# Tractive_System_Board_Rev1.net
KiCad netlist of a schematic drawn in EAGLE
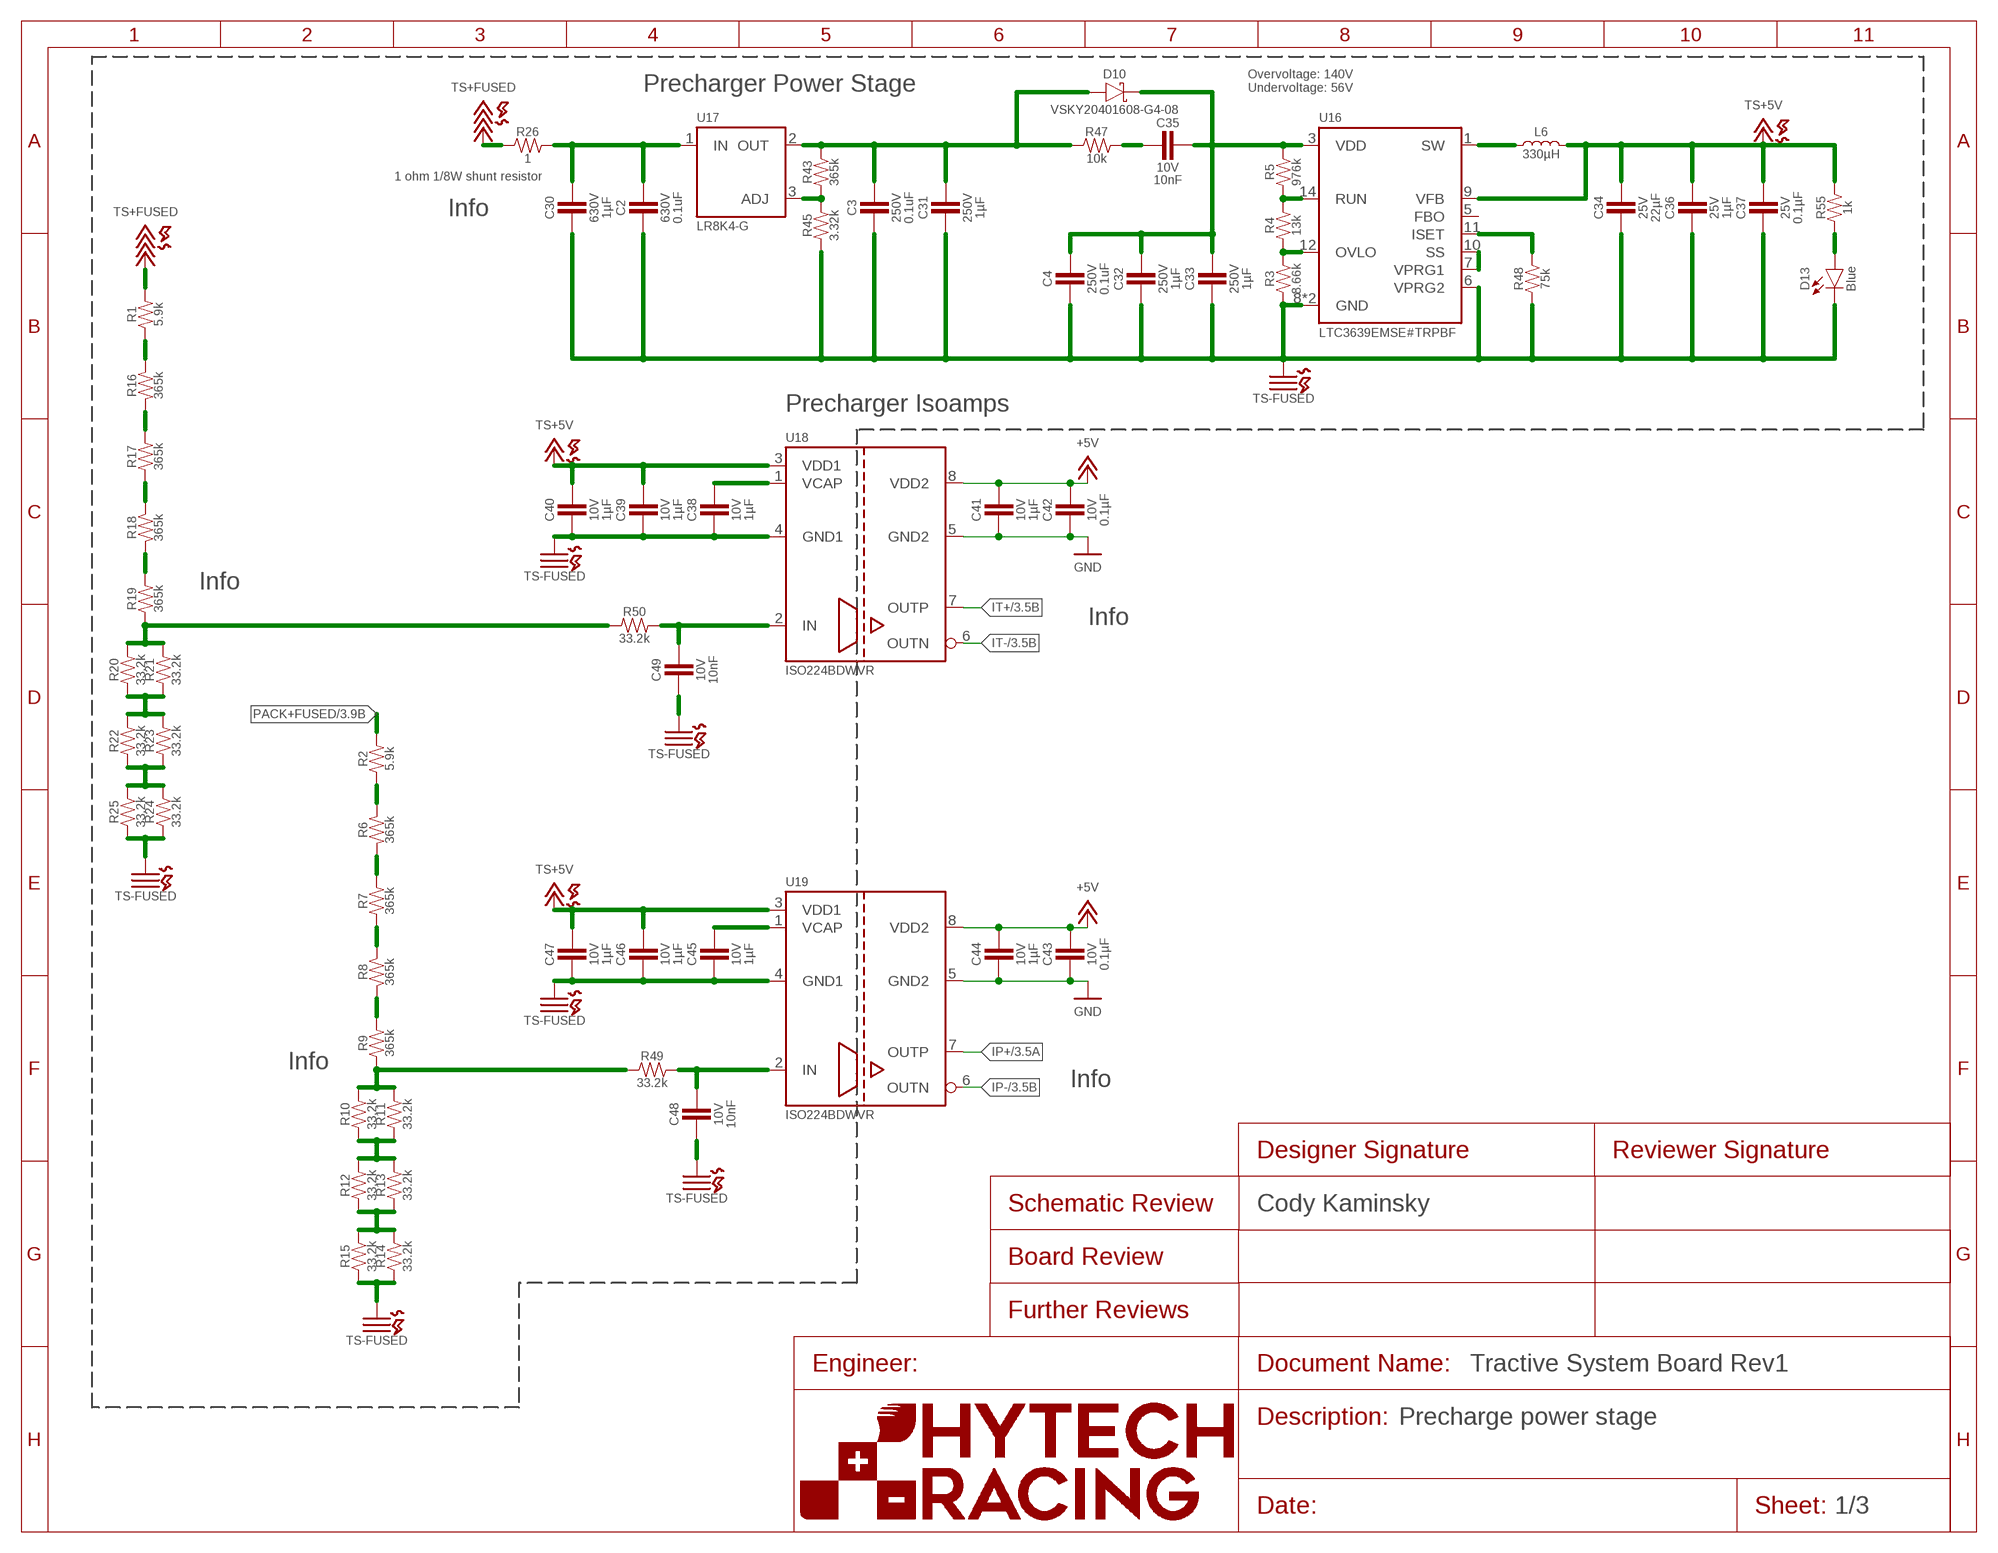
[diagram p0: schematic, sheet 1]
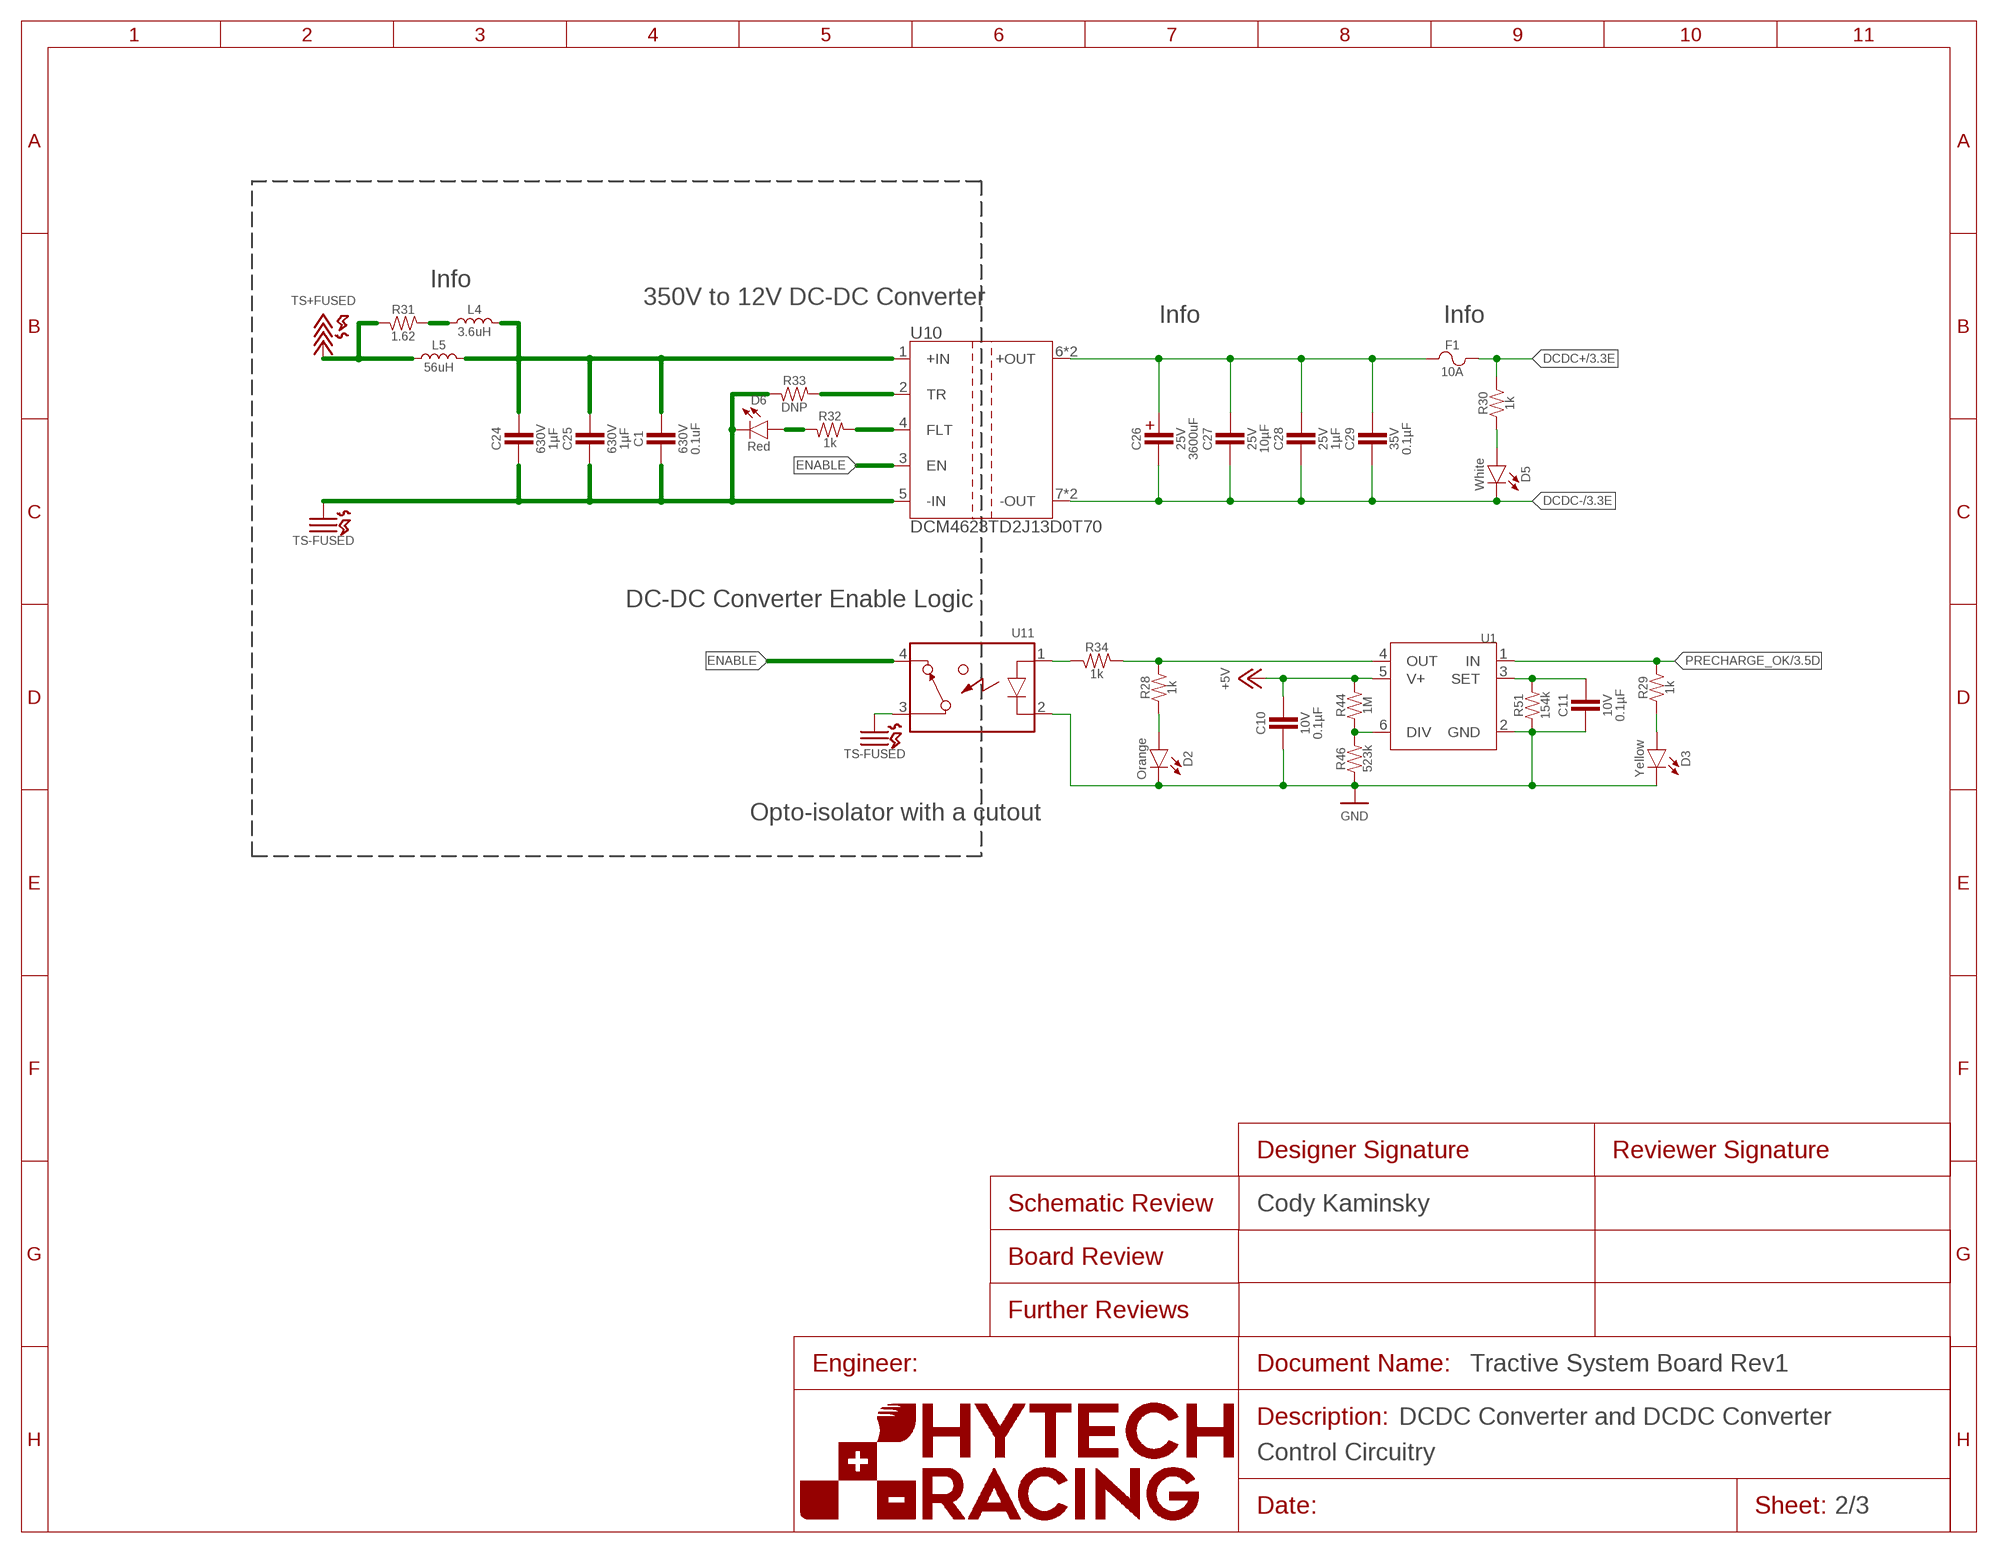
[diagram p1: schematic, sheet 2]
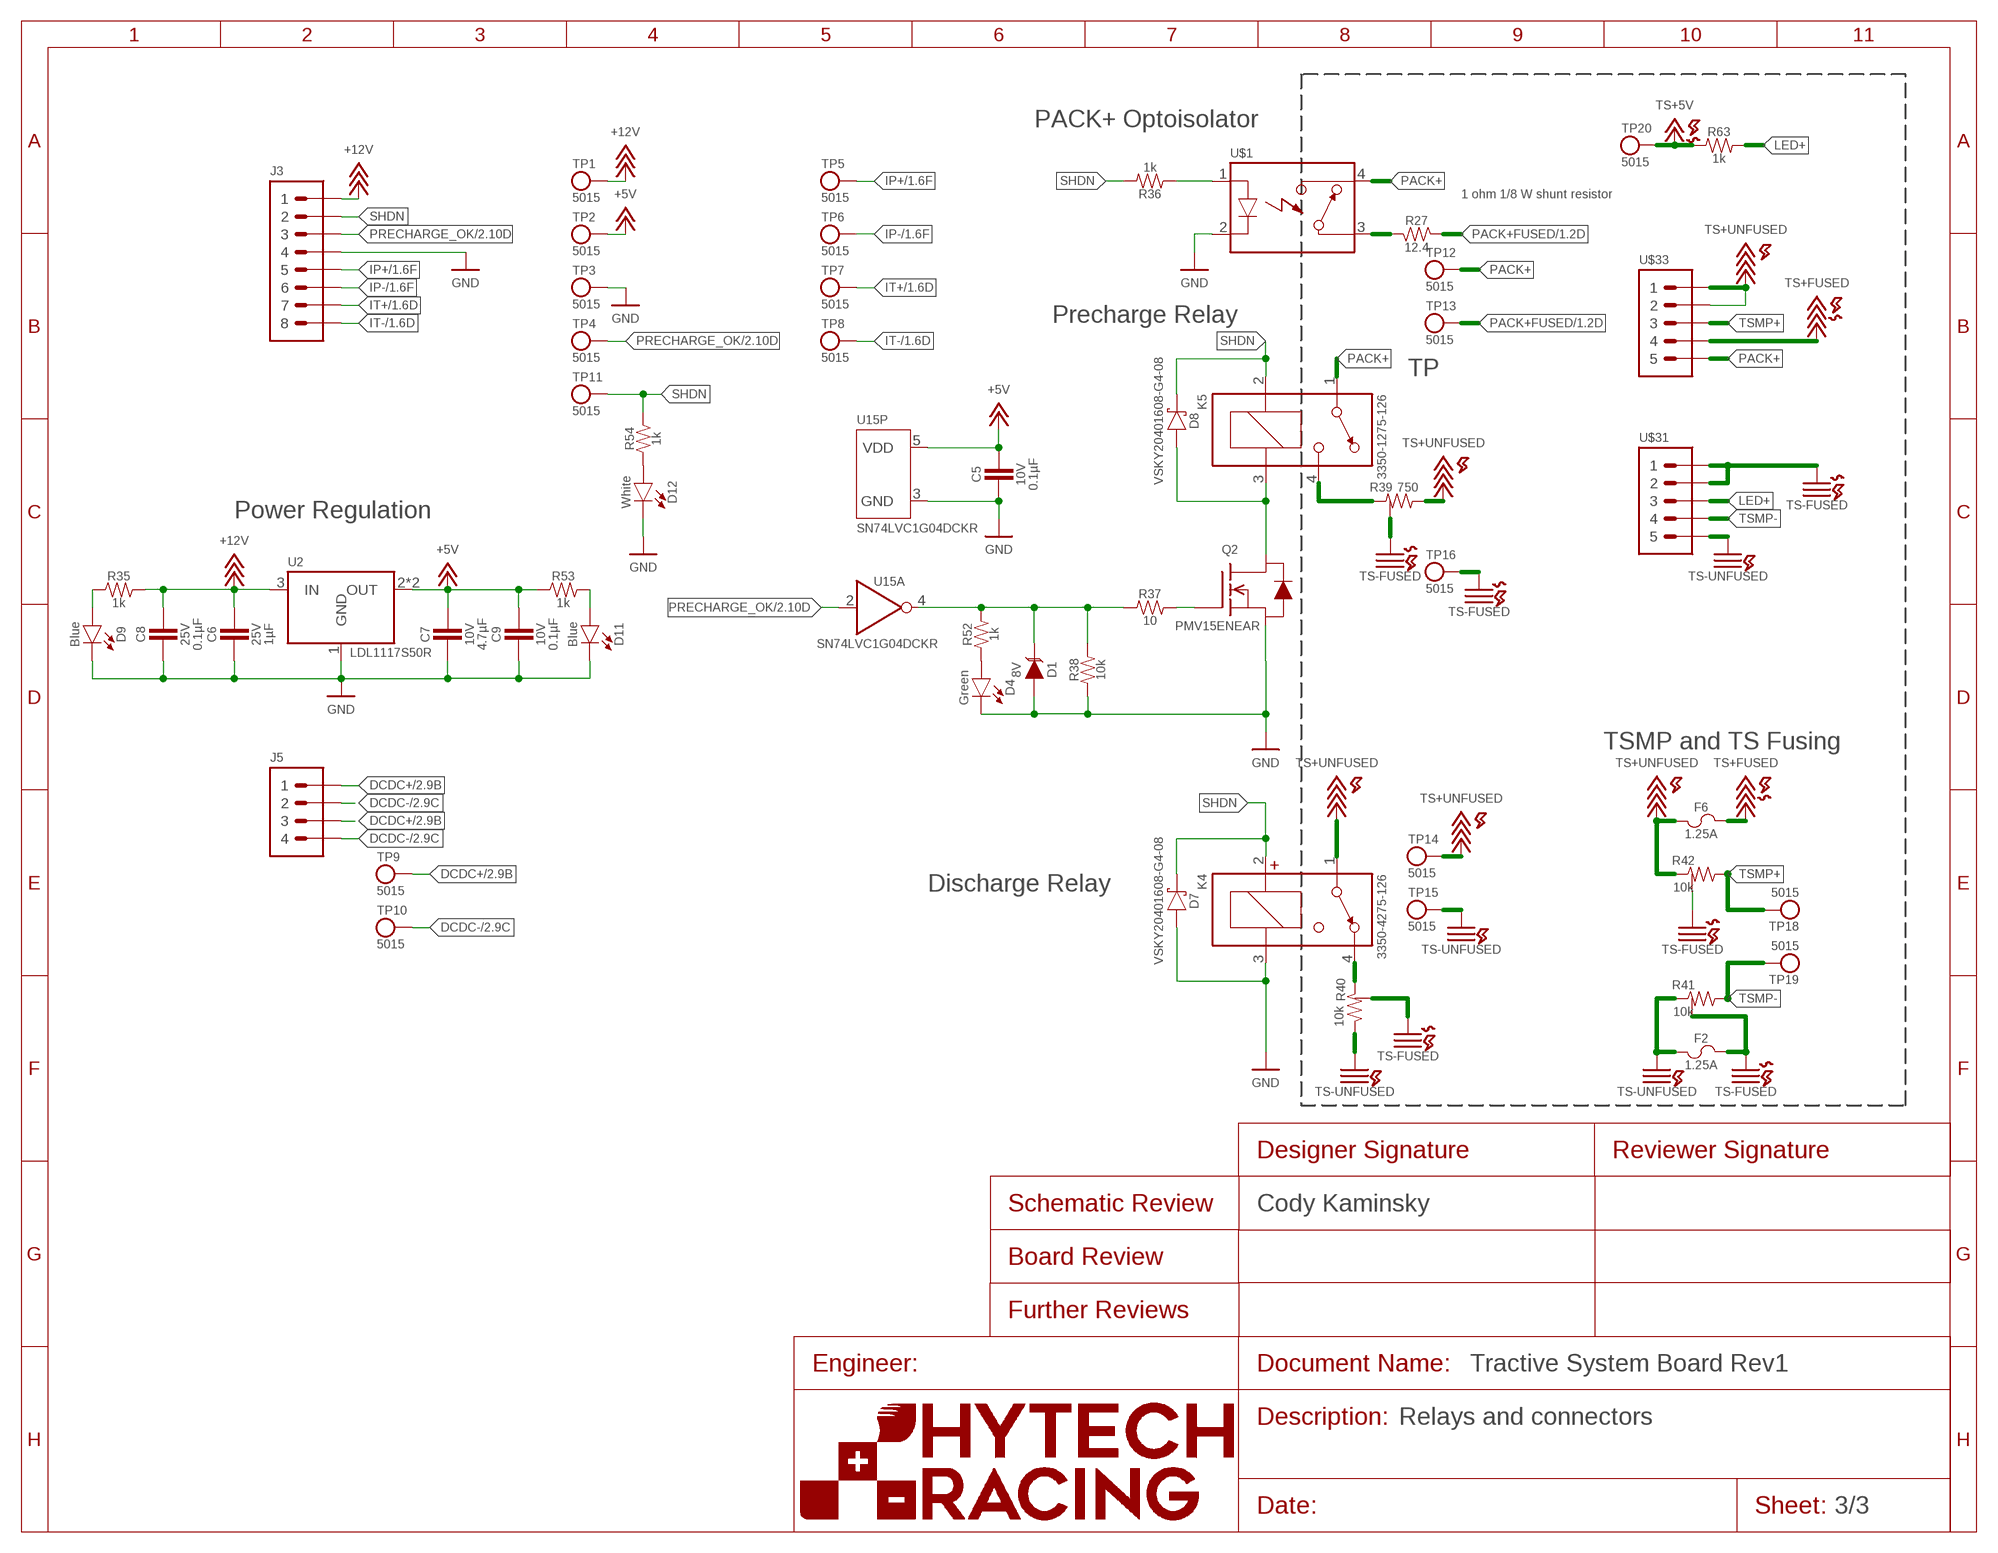
[diagram p2: schematic, sheet 3]

(export (version "E")
  (design (tool "Eeschema 10.0.6"))
  (components
    (comp (ref "C1")
      (value "CAPACITOR_2220_630V_0.1UF")
      (footprint "eagle-import:2220-CAP")
      (fields
        (field (name "CAPACITANCE") "0.1uF")
        (field (name "MANUFACTURER") "TDK Coporation")
        (field (name "MPN") "C5750CH2J104K280KC")
        (field (name "TOLERANCE") "10%")
        (field (name "VOLTAGE") "630V")
      )
      (libsource (lib "eagle-import") (part "CAPACITOR_?_2220630V_0.1UF"))
    )
    (comp (ref "C10")
      (value "CAPACITOR_0603_10V_0.1UF")
      (footprint "eagle-import:0603-CAP")
      (fields
        (field (name "CAPACITANCE") "0.1µF")
        (field (name "MANUFACTURER") "Vishay Vitramon")
        (field (name "MPN") "VJ0603Y104JXQPW1BC")
        (field (name "TOLERANCE") "5%")
        (field (name "VOLTAGE") "10V")
      )
      (libsource (lib "eagle-import") (part "CAPACITOR_?_060310V_0.1UF"))
    )
    (comp (ref "C11")
      (value "CAPACITOR_0603_10V_0.1UF")
      (footprint "eagle-import:0603-CAP")
      (fields
        (field (name "CAPACITANCE") "0.1µF")
        (field (name "MANUFACTURER") "Vishay Vitramon")
        (field (name "MPN") "VJ0603Y104JXQPW1BC")
        (field (name "TOLERANCE") "5%")
        (field (name "VOLTAGE") "10V")
      )
      (libsource (lib "eagle-import") (part "CAPACITOR_?_060310V_0.1UF"))
    )
    (comp (ref "C24")
      (value "CAPACITOR_2220_630V_1UF")
      (footprint "eagle-import:2220-CAP")
      (fields
        (field (name "CAPACITANCE") "1µF")
        (field (name "MANUFACTURER") "Knowles Syfer")
        (field (name "MPN") "2220Y6300105KXTWS2")
        (field (name "TOLERANCE") "10%")
        (field (name "VOLTAGE") "630V")
      )
      (libsource (lib "eagle-import") (part "CAPACITOR_?_2220630V_1UF"))
    )
    (comp (ref "C25")
      (value "CAPACITOR_2220_630V_1UF")
      (footprint "eagle-import:2220-CAP")
      (fields
        (field (name "CAPACITANCE") "1µF")
        (field (name "MANUFACTURER") "Knowles Syfer")
        (field (name "MPN") "2220Y6300105KXTWS2")
        (field (name "TOLERANCE") "10%")
        (field (name "VOLTAGE") "630V")
      )
      (libsource (lib "eagle-import") (part "CAPACITOR_?_2220630V_1UF"))
    )
    (comp (ref "C26")
      (value "CAPACITOR_POLAR__3600UF")
      (footprint "eagle-import:EKYC_MM")
      (fields
        (field (name "CAPACITANCE") "3600uF")
        (field (name "MANUFACTURER") "United Chemi-con")
        (field (name "MPN") "EKYC250ELL362ML20S")
        (field (name "VOLTAGE") "25V")
      )
      (libsource (lib "eagle-import") (part "CAPACITOR_POLAR_?_3600UF"))
    )
    (comp (ref "C27")
      (value "CAPACITOR_0603_25V_10UF")
      (footprint "eagle-import:0603-CAP")
      (fields
        (field (name "CAPACITANCE") "10µF")
        (field (name "MANUFACTURER") "Murata Electronics")
        (field (name "MPN") "GRM188R61E106MA73D")
        (field (name "TOLERANCE") "20%")
        (field (name "VOLTAGE") "25V")
      )
      (libsource (lib "eagle-import") (part "CAPACITOR_?_060325V_10UF"))
    )
    (comp (ref "C28")
      (value "CAPACITOR_0603_25V_1UF")
      (footprint "eagle-import:0603-CAP")
      (fields
        (field (name "CAPACITANCE") "1µF")
        (field (name "MANUFACTURER") "Samsung Electro-Mechanics")
        (field (name "MPN") "CL10B105KA8NNNC")
        (field (name "TOLERANCE") "10%")
        (field (name "VOLTAGE") "25V")
      )
      (libsource (lib "eagle-import") (part "CAPACITOR_?_060325V_1UF"))
    )
    (comp (ref "C29")
      (value "CAPACITOR_0603_35V_0.1UF")
      (footprint "eagle-import:0603-CAP")
      (fields
        (field (name "CAPACITANCE") "0.1µF")
        (field (name "MANUFACTURER") "Taiyo Yuden")
        (field (name "MPN") "GMK107B7104KAHT")
        (field (name "TOLERANCE") "10%")
        (field (name "VOLTAGE") "35V")
      )
      (libsource (lib "eagle-import") (part "CAPACITOR_?_060335V_0.1UF"))
    )
    (comp (ref "D2")
      (value "LED_0603_ORANGE")
      (footprint "eagle-import:0603-LED")
      (fields
        (field (name "COLOR") "Orange")
        (field (name "MANUFACTURER") "Kingbright")
        (field (name "MPN") "APT1608SECK")
      )
      (libsource (lib "eagle-import") (part "LED_?_0603ORANGE"))
    )
    (comp (ref "D3")
      (value "LED_0603_YELLOW")
      (footprint "eagle-import:0603-LED")
      (fields
        (field (name "COLOR") "Yellow")
        (field (name "MANUFACTURER") "Kingbright")
        (field (name "MPN") "APT1608SYCK/J3-PRV")
      )
      (libsource (lib "eagle-import") (part "LED_?_0603YELLOW"))
    )
    (comp (ref "D5")
      (value "LED_0603_WHITE")
      (footprint "eagle-import:0603-LED")
      (fields
        (field (name "COLOR") "White")
        (field (name "MANUFACTURER") "Bivar Inc.")
        (field (name "MPN") "SM0603UWC")
      )
      (libsource (lib "eagle-import") (part "LED_?_0603WHITE"))
    )
    (comp (ref "D6")
      (value "LED_0603_RED")
      (footprint "eagle-import:0603-LED")
      (fields
        (field (name "COLOR") "Red")
        (field (name "MANUFACTURER") "Kingbright")
        (field (name "MPN") "APT1608SECK/J3-PRV")
      )
      (libsource (lib "eagle-import") (part "LED_?_0603RED"))
    )
    (comp (ref "F1")
      (value "FUSE_MB_10")
      (footprint "eagle-import:MINI-BLADE_FUSE_HOLDER")
      (fields
        (field (name "CURRENT") "10A")
        (field (name "MANUFACTURER") "Littelfuse Inc.")
        (field (name "MPN") "0297010.WXNV")
        (field (name "VOLTAGE") "32V")
      )
      (libsource (lib "eagle-import") (part "FUSE_?_MB10"))
    )
    (comp (ref "L4")
      (value "INDUCTOR_PA4334_3.6UH")
      (footprint "eagle-import:PA4334")
      (fields
        (field (name "INDUCTANCE") "3.6uH")
        (field (name "MANUFACTURER") "Pulse Electonics Company")
        (field (name "MPN") "PA4334.362NLT")
        (field (name "TOLERANCE") "20%")
      )
      (libsource (lib "eagle-import") (part "INDUCTOR_?_PA43343.6UH"))
    )
    (comp (ref "L5")
      (value "INDUCTOR_WELMHI_56UH")
      (footprint "eagle-import:WE-LMHI")
      (fields
        (field (name "INDUCTANCE") "56uH")
        (field (name "MANUFACTURER") "Wurth Elektronik")
        (field (name "MPN") "74437349560")
        (field (name "TOLERANCE") "20%")
      )
      (libsource (lib "eagle-import") (part "INDUCTOR_?_WELMHI56UH"))
    )
    (comp (ref "R28")
      (value "RESISTOR_0603_1K")
      (footprint "eagle-import:0603-RES")
      (fields
        (field (name "MANUFACTURER") "Yageo")
        (field (name "MPN") "RC0603FR-071KL")
        (field (name "POWER") "0.1W")
        (field (name "RESISTANCE") "1k")
      )
      (libsource (lib "eagle-import") (part "RESISTOR_?_06031K"))
    )
    (comp (ref "R29")
      (value "RESISTOR_0603_1K")
      (footprint "eagle-import:0603-RES")
      (fields
        (field (name "MANUFACTURER") "Yageo")
        (field (name "MPN") "RC0603FR-071KL")
        (field (name "POWER") "0.1W")
        (field (name "RESISTANCE") "1k")
      )
      (libsource (lib "eagle-import") (part "RESISTOR_?_06031K"))
    )
    (comp (ref "R30")
      (value "RESISTOR_0603_1K")
      (footprint "eagle-import:0603-RES")
      (fields
        (field (name "MANUFACTURER") "Yageo")
        (field (name "MPN") "RC0603FR-071KL")
        (field (name "POWER") "0.1W")
        (field (name "RESISTANCE") "1k")
      )
      (libsource (lib "eagle-import") (part "RESISTOR_?_06031K"))
    )
    (comp (ref "R31")
      (value "RESISTOR_0603_1.62")
      (footprint "eagle-import:0603-RES")
      (fields
        (field (name "MANUFACTURER") "TE Conductivity Passive Product")
        (field (name "MPN") "CPF0603B1R62E1")
        (field (name "POWER") "0.1W")
        (field (name "RESISTANCE") "1.62")
      )
      (libsource (lib "eagle-import") (part "RESISTOR_?_06031.62"))
    )
    (comp (ref "R32")
      (value "RESISTOR_0603_1K")
      (footprint "eagle-import:0603-RES")
      (fields
        (field (name "MANUFACTURER") "Yageo")
        (field (name "MPN") "RC0603FR-071KL")
        (field (name "POWER") "0.1W")
        (field (name "RESISTANCE") "1k")
      )
      (libsource (lib "eagle-import") (part "RESISTOR_?_06031K"))
    )
    (comp (ref "R33")
      (value "RESISTOR_0603_DNP")
      (footprint "eagle-import:0603-RES")
      (fields (field (name "RESISTANCE") "DNP"))
      (libsource (lib "eagle-import") (part "RESISTOR_?_0603DNP"))
    )
    (comp (ref "R34")
      (value "RESISTOR_0603_1K")
      (footprint "eagle-import:0603-RES")
      (fields
        (field (name "MANUFACTURER") "Yageo")
        (field (name "MPN") "RC0603FR-071KL")
        (field (name "POWER") "0.1W")
        (field (name "RESISTANCE") "1k")
      )
      (libsource (lib "eagle-import") (part "RESISTOR_?_06031K"))
    )
    (comp (ref "R44")
      (value "RESISTOR_0805_1M")
      (footprint "eagle-import:0805-RES")
      (fields
        (field (name "MANUFACTURER") "Panasonic Electronic Components")
        (field (name "MPN") "ERJ-PB6B1004V")
        (field (name "POWER") "0.25W")
        (field (name "RESISTANCE") "1M")
      )
      (libsource (lib "eagle-import") (part "RESISTOR_?_08051M"))
    )
    (comp (ref "R46")
      (value "RESISTOR_0805_523K")
      (footprint "eagle-import:0805-RES")
      (fields
        (field (name "MANUFACTURER") "Panasonic Electronic Components")
        (field (name "MPN") "ERJ-PB6B5233V")
        (field (name "POWER") "0.25W")
        (field (name "RESISTANCE") "523k")
      )
      (libsource (lib "eagle-import") (part "RESISTOR_?_0805523K"))
    )
    (comp (ref "R51")
      (value "RESISTOR_0603_154K")
      (footprint "eagle-import:0603-RES")
      (fields
        (field (name "MANUFACTURER") "Panasonic Electronic Components")
        (field (name "MPN") "ERA-3AEB1543V")
        (field (name "POWER") "0.1W")
        (field (name "RESISTANCE") "154k")
      )
      (libsource (lib "eagle-import") (part "RESISTOR_?_0603154K"))
    )
    (comp (ref "U1")
      (value "LTC6994_1")
      (footprint "eagle-import:SOT-23-6")
      (fields (field (name "MANUFACTURER") "Analog Electronics") (field (name "MPN") "LTC6994CS6-1#TRMPBF"))
      (libsource (lib "eagle-import") (part "LTC6994_1"))
    )
    (comp (ref "U10")
      (value "DCM4623TD2J13D0T70")
      (footprint "eagle-import:DCM4623")
      (fields (field (name "MANUFACTURER") "Vicor"))
      (libsource (lib "eagle-import") (part "DCM4623TD2J13D0T70"))
    )
    (comp (ref "U11")
      (value "RELAY_SOLIDSTATE_NC_AG")
      (footprint "eagle-import:DIP-4_AIRGAP")
      (fields (field (name "MPN") "AQY414EHA") (field (name "MANUFACTURER") "Panasonic Industrial Devices"))
      (libsource (lib "eagle-import") (part "RELAY_SOLIDSTATE_NC_?AG"))
    )
    (comp (ref "C2")
      (value "CAPACITOR_2220_630V_0.1UF")
      (footprint "eagle-import:2220-CAP")
      (fields
        (field (name "CAPACITANCE") "0.1uF")
        (field (name "MANUFACTURER") "TDK Coporation")
        (field (name "MPN") "C5750CH2J104K280KC")
        (field (name "TOLERANCE") "10%")
        (field (name "VOLTAGE") "630V")
      )
      (libsource (lib "eagle-import") (part "CAPACITOR_?_2220630V_0.1UF"))
    )
    (comp (ref "C3")
      (value "CAPACITOR_1206_250V_0.1UF")
      (footprint "eagle-import:1206-CAP")
      (fields
        (field (name "CAPACITANCE") "0.1uF")
        (field (name "MANUFACTURER") "TDK Corporation")
        (field (name "MPN") "C3216X7R2E104K160AM")
        (field (name "TOLERANCE") "10%")
        (field (name "VOLTAGE") "250V")
      )
      (libsource (lib "eagle-import") (part "CAPACITOR_?_1206250V_0.1UF"))
    )
    (comp (ref "C4")
      (value "CAPACITOR_1206_250V_0.1UF")
      (footprint "eagle-import:1206-CAP")
      (fields
        (field (name "CAPACITANCE") "0.1uF")
        (field (name "MANUFACTURER") "TDK Corporation")
        (field (name "MPN") "C3216X7R2E104K160AM")
        (field (name "TOLERANCE") "10%")
        (field (name "VOLTAGE") "250V")
      )
      (libsource (lib "eagle-import") (part "CAPACITOR_?_1206250V_0.1UF"))
    )
    (comp (ref "C30")
      (value "CAPACITOR_2220_630V_1UF")
      (footprint "eagle-import:2220-CAP")
      (fields
        (field (name "CAPACITANCE") "1µF")
        (field (name "MANUFACTURER") "Knowles Syfer")
        (field (name "MPN") "2220Y6300105KXTWS2")
        (field (name "TOLERANCE") "10%")
        (field (name "VOLTAGE") "630V")
      )
      (libsource (lib "eagle-import") (part "CAPACITOR_?_2220630V_1UF"))
    )
    (comp (ref "C31")
      (value "CAPACITOR_2220_250V_1UF")
      (footprint "eagle-import:2220-CAP")
      (fields
        (field (name "CAPACITANCE") "1µF")
        (field (name "MANUFACTURER") "TDK Corporation")
        (field (name "MPN") "C5750X7R2E105K230KA")
        (field (name "TOLERANCE") "10%")
        (field (name "VOLTAGE") "250V")
      )
      (libsource (lib "eagle-import") (part "CAPACITOR_?_2220250V_1UF"))
    )
    (comp (ref "C32")
      (value "CAPACITOR_2220_250V_1UF")
      (footprint "eagle-import:2220-CAP")
      (fields
        (field (name "CAPACITANCE") "1µF")
        (field (name "MANUFACTURER") "TDK Corporation")
        (field (name "MPN") "C5750X7R2E105K230KA")
        (field (name "TOLERANCE") "10%")
        (field (name "VOLTAGE") "250V")
      )
      (libsource (lib "eagle-import") (part "CAPACITOR_?_2220250V_1UF"))
    )
    (comp (ref "C33")
      (value "CAPACITOR_2220_250V_1UF")
      (footprint "eagle-import:2220-CAP")
      (fields
        (field (name "CAPACITANCE") "1µF")
        (field (name "MANUFACTURER") "TDK Corporation")
        (field (name "MPN") "C5750X7R2E105K230KA")
        (field (name "TOLERANCE") "10%")
        (field (name "VOLTAGE") "250V")
      )
      (libsource (lib "eagle-import") (part "CAPACITOR_?_2220250V_1UF"))
    )
    (comp (ref "C34")
      (value "CAPACITOR_0805_25V_22UF")
      (footprint "eagle-import:0805-CAP")
      (fields
        (field (name "CAPACITANCE") "22µF")
        (field (name "MANUFACTURER") "Yageo")
        (field (name "MPN") "CC0805MKX5R8BB226")
        (field (name "TOLERANCE") "20%")
        (field (name "VOLTAGE") "25V")
      )
      (libsource (lib "eagle-import") (part "CAPACITOR_?_080525V_22UF"))
    )
    (comp (ref "C35")
      (value "CAPACITOR_0603_10V_10NF")
      (footprint "eagle-import:0603-CAP")
      (fields
        (field (name "CAPACITANCE") "10nF")
        (field (name "MANUFACTURER") "Yageo")
        (field (name "MPN") "CC0603KRX7R6BB103")
        (field (name "TOLERANCE") "10%")
        (field (name "VOLTAGE") "10V")
      )
      (libsource (lib "eagle-import") (part "CAPACITOR_?_060310V_10NF"))
    )
    (comp (ref "C36")
      (value "CAPACITOR_0603_25V_1UF")
      (footprint "eagle-import:0603-CAP")
      (fields
        (field (name "CAPACITANCE") "1µF")
        (field (name "MANUFACTURER") "Samsung Electro-Mechanics")
        (field (name "MPN") "CL10B105KA8NNNC")
        (field (name "TOLERANCE") "10%")
        (field (name "VOLTAGE") "25V")
      )
      (libsource (lib "eagle-import") (part "CAPACITOR_?_060325V_1UF"))
    )
    (comp (ref "C37")
      (value "CAPACITOR_0603_25V_0.1UF")
      (footprint "eagle-import:0603-CAP")
      (fields
        (field (name "CAPACITANCE") "0.1µF")
        (field (name "MANUFACTURER") "Samsung Electro-Mechanics")
        (field (name "MPN") "CL10B104KA8NNNC")
        (field (name "TOLERANCE") "10%")
        (field (name "VOLTAGE") "25V")
      )
      (libsource (lib "eagle-import") (part "CAPACITOR_?_060325V_0.1UF"))
    )
    (comp (ref "C38")
      (value "CAPACITOR_0603_10V_1UF")
      (footprint "eagle-import:0603-CAP")
      (fields
        (field (name "CAPACITANCE") "1µF")
        (field (name "MANUFACTURER") "Yageo")
        (field (name "MPN") "CC0603KRX7R6BB105")
        (field (name "TOLERANCE") "10%")
        (field (name "VOLTAGE") "10V")
      )
      (libsource (lib "eagle-import") (part "CAPACITOR_?_060310V_1UF"))
    )
    (comp (ref "C39")
      (value "CAPACITOR_0603_10V_1UF")
      (footprint "eagle-import:0603-CAP")
      (fields
        (field (name "CAPACITANCE") "1µF")
        (field (name "MANUFACTURER") "Yageo")
        (field (name "MPN") "CC0603KRX7R6BB105")
        (field (name "TOLERANCE") "10%")
        (field (name "VOLTAGE") "10V")
      )
      (libsource (lib "eagle-import") (part "CAPACITOR_?_060310V_1UF"))
    )
    (comp (ref "C40")
      (value "CAPACITOR_0603_10V_1UF")
      (footprint "eagle-import:0603-CAP")
      (fields
        (field (name "CAPACITANCE") "1µF")
        (field (name "MANUFACTURER") "Yageo")
        (field (name "MPN") "CC0603KRX7R6BB105")
        (field (name "TOLERANCE") "10%")
        (field (name "VOLTAGE") "10V")
      )
      (libsource (lib "eagle-import") (part "CAPACITOR_?_060310V_1UF"))
    )
    (comp (ref "C41")
      (value "CAPACITOR_0603_10V_1UF")
      (footprint "eagle-import:0603-CAP")
      (fields
        (field (name "CAPACITANCE") "1µF")
        (field (name "MANUFACTURER") "Yageo")
        (field (name "MPN") "CC0603KRX7R6BB105")
        (field (name "TOLERANCE") "10%")
        (field (name "VOLTAGE") "10V")
      )
      (libsource (lib "eagle-import") (part "CAPACITOR_?_060310V_1UF"))
    )
    (comp (ref "C42")
      (value "CAPACITOR_0603_10V_0.1UF")
      (footprint "eagle-import:0603-CAP")
      (fields
        (field (name "CAPACITANCE") "0.1µF")
        (field (name "MANUFACTURER") "Vishay Vitramon")
        (field (name "MPN") "VJ0603Y104JXQPW1BC")
        (field (name "TOLERANCE") "5%")
        (field (name "VOLTAGE") "10V")
      )
      (libsource (lib "eagle-import") (part "CAPACITOR_?_060310V_0.1UF"))
    )
    (comp (ref "C43")
      (value "CAPACITOR_0603_10V_0.1UF")
      (footprint "eagle-import:0603-CAP")
      (fields
        (field (name "CAPACITANCE") "0.1µF")
        (field (name "MANUFACTURER") "Vishay Vitramon")
        (field (name "MPN") "VJ0603Y104JXQPW1BC")
        (field (name "TOLERANCE") "5%")
        (field (name "VOLTAGE") "10V")
      )
      (libsource (lib "eagle-import") (part "CAPACITOR_?_060310V_0.1UF"))
    )
    (comp (ref "C44")
      (value "CAPACITOR_0603_10V_1UF")
      (footprint "eagle-import:0603-CAP")
      (fields
        (field (name "CAPACITANCE") "1µF")
        (field (name "MANUFACTURER") "Yageo")
        (field (name "MPN") "CC0603KRX7R6BB105")
        (field (name "TOLERANCE") "10%")
        (field (name "VOLTAGE") "10V")
      )
      (libsource (lib "eagle-import") (part "CAPACITOR_?_060310V_1UF"))
    )
    (comp (ref "C45")
      (value "CAPACITOR_0603_10V_1UF")
      (footprint "eagle-import:0603-CAP")
      (fields
        (field (name "CAPACITANCE") "1µF")
        (field (name "MANUFACTURER") "Yageo")
        (field (name "MPN") "CC0603KRX7R6BB105")
        (field (name "TOLERANCE") "10%")
        (field (name "VOLTAGE") "10V")
      )
      (libsource (lib "eagle-import") (part "CAPACITOR_?_060310V_1UF"))
    )
    (comp (ref "C46")
      (value "CAPACITOR_0603_10V_1UF")
      (footprint "eagle-import:0603-CAP")
      (fields
        (field (name "CAPACITANCE") "1µF")
        (field (name "MANUFACTURER") "Yageo")
        (field (name "MPN") "CC0603KRX7R6BB105")
        (field (name "TOLERANCE") "10%")
        (field (name "VOLTAGE") "10V")
      )
      (libsource (lib "eagle-import") (part "CAPACITOR_?_060310V_1UF"))
    )
    (comp (ref "C47")
      (value "CAPACITOR_0603_10V_1UF")
      (footprint "eagle-import:0603-CAP")
      (fields
        (field (name "CAPACITANCE") "1µF")
        (field (name "MANUFACTURER") "Yageo")
        (field (name "MPN") "CC0603KRX7R6BB105")
        (field (name "TOLERANCE") "10%")
        (field (name "VOLTAGE") "10V")
      )
      (libsource (lib "eagle-import") (part "CAPACITOR_?_060310V_1UF"))
    )
    (comp (ref "C48")
      (value "CAPACITOR_0603_10V_10NF")
      (footprint "eagle-import:0603-CAP")
      (fields
        (field (name "CAPACITANCE") "10nF")
        (field (name "MANUFACTURER") "Yageo")
        (field (name "MPN") "CC0603KRX7R6BB103")
        (field (name "TOLERANCE") "10%")
        (field (name "VOLTAGE") "10V")
      )
      (libsource (lib "eagle-import") (part "CAPACITOR_?_060310V_10NF"))
    )
    (comp (ref "C49")
      (value "CAPACITOR_0603_10V_10NF")
      (footprint "eagle-import:0603-CAP")
      (fields
        (field (name "CAPACITANCE") "10nF")
        (field (name "MANUFACTURER") "Yageo")
        (field (name "MPN") "CC0603KRX7R6BB103")
        (field (name "TOLERANCE") "10%")
        (field (name "VOLTAGE") "10V")
      )
      (libsource (lib "eagle-import") (part "CAPACITOR_?_060310V_10NF"))
    )
    (comp (ref "D10")
      (value "SCHOTTKY")
      (footprint "eagle-import:CLP1608-2L")
      (fields
        (field (name "MPN") "VSKY20401608-G4-08")
        (field (name "MANUFACTURER") "Vishay General Semiconductor - Diodes Division")
      )
      (libsource (lib "eagle-import") (part "SCHOTTKY"))
    )
    (comp (ref "D13")
      (value "LED_0603_BLUE")
      (footprint "eagle-import:0603-LED")
      (fields
        (field (name "COLOR") "Blue")
        (field (name "MANUFACTURER") "Kingbright")
        (field (name "MPN") "APT1608VBC/D")
      )
      (libsource (lib "eagle-import") (part "LED_?_0603BLUE"))
    )
    (comp (ref "L6")
      (value "INDUCTOR_SRU1048_330UH")
      (footprint "eagle-import:SRU1048")
      (fields
        (field (name "INDUCTANCE") "330µH")
        (field (name "MANUFACTURER") "Bourns Inc.")
        (field (name "MPN") "SRU1048-331Y")
        (field (name "TOLERANCE") "30%")
      )
      (libsource (lib "eagle-import") (part "INDUCTOR_?_SRU1048330UH"))
    )
    (comp (ref "R1")
      (value "RESISTOR_0603_5.9K")
      (footprint "eagle-import:0603-RES")
      (fields
        (field (name "MANUFACTURER") "Panasonic Electronic Components")
        (field (name "MPN") "ERA-3AEB5901V")
        (field (name "POWER") "0.1W")
        (field (name "RESISTANCE") "5.9k")
      )
      (libsource (lib "eagle-import") (part "RESISTOR_?_06035.9K"))
    )
    (comp (ref "R2")
      (value "RESISTOR_0603_5.9K")
      (footprint "eagle-import:0603-RES")
      (fields
        (field (name "MANUFACTURER") "Panasonic Electronic Components")
        (field (name "MPN") "ERA-3AEB5901V")
        (field (name "POWER") "0.1W")
        (field (name "RESISTANCE") "5.9k")
      )
      (libsource (lib "eagle-import") (part "RESISTOR_?_06035.9K"))
    )
    (comp (ref "R3")
      (value "RESISTOR_0603_8.66K")
      (footprint "eagle-import:0603-RES")
      (fields
        (field (name "MANUFACTURER") "Yageo")
        (field (name "MPN") "RT0603BRD078K66L")
        (field (name "POWER") "0.1W")
        (field (name "RESISTANCE") "8.66k")
      )
      (libsource (lib "eagle-import") (part "RESISTOR_?_06038.66K"))
    )
    (comp (ref "R4")
      (value "RESISTOR_0603_13K")
      (footprint "eagle-import:0603-RES")
      (fields
        (field (name "MANUFACTURER") "Panasonic Electronic Components")
        (field (name "MPN") " ERJ-PB3B1302V")
        (field (name "POWER") "0.1W")
        (field (name "RESISTANCE") "13k")
      )
      (libsource (lib "eagle-import") (part "RESISTOR_?_060313K"))
    )
    (comp (ref "R5")
      (value "RESISTOR_0805_976K")
      (footprint "eagle-import:0805-RES")
      (fields
        (field (name "MANUFACTURER") "Panasonic Electronic Components")
        (field (name "MPN") "  ERJ-PB6B9763V")
        (field (name "POWER") "0.25W")
        (field (name "RESISTANCE") "976k")
      )
      (libsource (lib "eagle-import") (part "RESISTOR_?_0805976K"))
    )
    (comp (ref "R6")
      (value "RESISTOR_0805_365K")
      (footprint "eagle-import:0805-RES")
      (fields
        (field (name "MANUFACTURER") "Panasonic Electronic Components")
        (field (name "MPN") "ERJ-PB6B3653V")
        (field (name "POWER") "0.25W")
        (field (name "RESISTANCE") "365k")
      )
      (libsource (lib "eagle-import") (part "RESISTOR_?_0805365K"))
    )
    (comp (ref "R7")
      (value "RESISTOR_0805_365K")
      (footprint "eagle-import:0805-RES")
      (fields
        (field (name "MANUFACTURER") "Panasonic Electronic Components")
        (field (name "MPN") "ERJ-PB6B3653V")
        (field (name "POWER") "0.25W")
        (field (name "RESISTANCE") "365k")
      )
      (libsource (lib "eagle-import") (part "RESISTOR_?_0805365K"))
    )
    (comp (ref "R8")
      (value "RESISTOR_0805_365K")
      (footprint "eagle-import:0805-RES")
      (fields
        (field (name "MANUFACTURER") "Panasonic Electronic Components")
        (field (name "MPN") "ERJ-PB6B3653V")
        (field (name "POWER") "0.25W")
        (field (name "RESISTANCE") "365k")
      )
      (libsource (lib "eagle-import") (part "RESISTOR_?_0805365K"))
    )
    (comp (ref "R9")
      (value "RESISTOR_0805_365K")
      (footprint "eagle-import:0805-RES")
      (fields
        (field (name "MANUFACTURER") "Panasonic Electronic Components")
        (field (name "MPN") "ERJ-PB6B3653V")
        (field (name "POWER") "0.25W")
        (field (name "RESISTANCE") "365k")
      )
      (libsource (lib "eagle-import") (part "RESISTOR_?_0805365K"))
    )
    (comp (ref "R10")
      (value "RESISTOR_0603_33.2K")
      (footprint "eagle-import:0603-RES")
      (fields
        (field (name "MANUFACTURER") "Panasonic Electronic Components")
        (field (name "MPN") "ERJ-PB3B3322V")
        (field (name "POWER") "0.1W")
        (field (name "RESISTANCE") "33.2k")
      )
      (libsource (lib "eagle-import") (part "RESISTOR_?_060333.2K"))
    )
    (comp (ref "R11")
      (value "RESISTOR_0603_33.2K")
      (footprint "eagle-import:0603-RES")
      (fields
        (field (name "MANUFACTURER") "Panasonic Electronic Components")
        (field (name "MPN") "ERJ-PB3B3322V")
        (field (name "POWER") "0.1W")
        (field (name "RESISTANCE") "33.2k")
      )
      (libsource (lib "eagle-import") (part "RESISTOR_?_060333.2K"))
    )
    (comp (ref "R12")
      (value "RESISTOR_0603_33.2K")
      (footprint "eagle-import:0603-RES")
      (fields
        (field (name "MANUFACTURER") "Panasonic Electronic Components")
        (field (name "MPN") "ERJ-PB3B3322V")
        (field (name "POWER") "0.1W")
        (field (name "RESISTANCE") "33.2k")
      )
      (libsource (lib "eagle-import") (part "RESISTOR_?_060333.2K"))
    )
    (comp (ref "R13")
      (value "RESISTOR_0603_33.2K")
      (footprint "eagle-import:0603-RES")
      (fields
        (field (name "MANUFACTURER") "Panasonic Electronic Components")
        (field (name "MPN") "ERJ-PB3B3322V")
        (field (name "POWER") "0.1W")
        (field (name "RESISTANCE") "33.2k")
      )
      (libsource (lib "eagle-import") (part "RESISTOR_?_060333.2K"))
    )
    (comp (ref "R14")
      (value "RESISTOR_0603_33.2K")
      (footprint "eagle-import:0603-RES")
      (fields
        (field (name "MANUFACTURER") "Panasonic Electronic Components")
        (field (name "MPN") "ERJ-PB3B3322V")
        (field (name "POWER") "0.1W")
        (field (name "RESISTANCE") "33.2k")
      )
      (libsource (lib "eagle-import") (part "RESISTOR_?_060333.2K"))
    )
    (comp (ref "R15")
      (value "RESISTOR_0603_33.2K")
      (footprint "eagle-import:0603-RES")
      (fields
        (field (name "MANUFACTURER") "Panasonic Electronic Components")
        (field (name "MPN") "ERJ-PB3B3322V")
        (field (name "POWER") "0.1W")
        (field (name "RESISTANCE") "33.2k")
      )
      (libsource (lib "eagle-import") (part "RESISTOR_?_060333.2K"))
    )
    (comp (ref "R16")
      (value "RESISTOR_0805_365K")
      (footprint "eagle-import:0805-RES")
      (fields
        (field (name "MANUFACTURER") "Panasonic Electronic Components")
        (field (name "MPN") "ERJ-PB6B3653V")
        (field (name "POWER") "0.25W")
        (field (name "RESISTANCE") "365k")
      )
      (libsource (lib "eagle-import") (part "RESISTOR_?_0805365K"))
    )
    (comp (ref "R17")
      (value "RESISTOR_0805_365K")
      (footprint "eagle-import:0805-RES")
      (fields
        (field (name "MANUFACTURER") "Panasonic Electronic Components")
        (field (name "MPN") "ERJ-PB6B3653V")
        (field (name "POWER") "0.25W")
        (field (name "RESISTANCE") "365k")
      )
      (libsource (lib "eagle-import") (part "RESISTOR_?_0805365K"))
    )
    (comp (ref "R18")
      (value "RESISTOR_0805_365K")
      (footprint "eagle-import:0805-RES")
      (fields
        (field (name "MANUFACTURER") "Panasonic Electronic Components")
        (field (name "MPN") "ERJ-PB6B3653V")
        (field (name "POWER") "0.25W")
        (field (name "RESISTANCE") "365k")
      )
      (libsource (lib "eagle-import") (part "RESISTOR_?_0805365K"))
    )
    (comp (ref "R19")
      (value "RESISTOR_0805_365K")
      (footprint "eagle-import:0805-RES")
      (fields
        (field (name "MANUFACTURER") "Panasonic Electronic Components")
        (field (name "MPN") "ERJ-PB6B3653V")
        (field (name "POWER") "0.25W")
        (field (name "RESISTANCE") "365k")
      )
      (libsource (lib "eagle-import") (part "RESISTOR_?_0805365K"))
    )
    (comp (ref "R20")
      (value "RESISTOR_0603_33.2K")
      (footprint "eagle-import:0603-RES")
      (fields
        (field (name "MANUFACTURER") "Panasonic Electronic Components")
        (field (name "MPN") "ERJ-PB3B3322V")
        (field (name "POWER") "0.1W")
        (field (name "RESISTANCE") "33.2k")
      )
      (libsource (lib "eagle-import") (part "RESISTOR_?_060333.2K"))
    )
    (comp (ref "R21")
      (value "RESISTOR_0603_33.2K")
      (footprint "eagle-import:0603-RES")
      (fields
        (field (name "MANUFACTURER") "Panasonic Electronic Components")
        (field (name "MPN") "ERJ-PB3B3322V")
        (field (name "POWER") "0.1W")
        (field (name "RESISTANCE") "33.2k")
      )
      (libsource (lib "eagle-import") (part "RESISTOR_?_060333.2K"))
    )
    (comp (ref "R22")
      (value "RESISTOR_0603_33.2K")
      (footprint "eagle-import:0603-RES")
      (fields
        (field (name "MANUFACTURER") "Panasonic Electronic Components")
        (field (name "MPN") "ERJ-PB3B3322V")
        (field (name "POWER") "0.1W")
        (field (name "RESISTANCE") "33.2k")
      )
      (libsource (lib "eagle-import") (part "RESISTOR_?_060333.2K"))
    )
    (comp (ref "R23")
      (value "RESISTOR_0603_33.2K")
      (footprint "eagle-import:0603-RES")
      (fields
        (field (name "MANUFACTURER") "Panasonic Electronic Components")
        (field (name "MPN") "ERJ-PB3B3322V")
        (field (name "POWER") "0.1W")
        (field (name "RESISTANCE") "33.2k")
      )
      (libsource (lib "eagle-import") (part "RESISTOR_?_060333.2K"))
    )
    (comp (ref "R24")
      (value "RESISTOR_0603_33.2K")
      (footprint "eagle-import:0603-RES")
      (fields
        (field (name "MANUFACTURER") "Panasonic Electronic Components")
        (field (name "MPN") "ERJ-PB3B3322V")
        (field (name "POWER") "0.1W")
        (field (name "RESISTANCE") "33.2k")
      )
      (libsource (lib "eagle-import") (part "RESISTOR_?_060333.2K"))
    )
    (comp (ref "R25")
      (value "RESISTOR_0603_33.2K")
      (footprint "eagle-import:0603-RES")
      (fields
        (field (name "MANUFACTURER") "Panasonic Electronic Components")
        (field (name "MPN") "ERJ-PB3B3322V")
        (field (name "POWER") "0.1W")
        (field (name "RESISTANCE") "33.2k")
      )
      (libsource (lib "eagle-import") (part "RESISTOR_?_060333.2K"))
    )
    (comp (ref "R26")
      (value "RESISTOR_0805_1")
      (footprint "eagle-import:0805-RES")
      (fields
        (field (name "MANUFACTURER") "Panasonic Electronic Components")
        (field (name "MPN") "ERJ-6RQF1R0V")
        (field (name "POWER") "0.125W")
        (field (name "RESISTANCE") "1")
      )
      (libsource (lib "eagle-import") (part "RESISTOR_?_08051"))
    )
    (comp (ref "R43")
      (value "RESISTOR_0805_365K")
      (footprint "eagle-import:0805-RES")
      (fields
        (field (name "MANUFACTURER") "Panasonic Electronic Components")
        (field (name "MPN") "ERJ-PB6B3653V")
        (field (name "POWER") "0.25W")
        (field (name "RESISTANCE") "365k")
      )
      (libsource (lib "eagle-import") (part "RESISTOR_?_0805365K"))
    )
    (comp (ref "R45")
      (value "RESISTOR_0603_3.32K")
      (footprint "eagle-import:0603-RES")
      (fields
        (field (name "MANUFACTURER") "Yageo")
        (field (name "MPN") "RT0603BRD073K32L")
        (field (name "POWER") "0.1W")
        (field (name "RESISTANCE") "3.32k")
      )
      (libsource (lib "eagle-import") (part "RESISTOR_?_06033.32K"))
    )
    (comp (ref "R47")
      (value "RESISTOR_0603_10K")
      (footprint "eagle-import:0603-RES")
      (fields
        (field (name "MANUFACTURER") "Yageo")
        (field (name "MPN") "RC0603FR-0710KL")
        (field (name "POWER") "0.1W")
        (field (name "RESISTANCE") "10k")
      )
      (libsource (lib "eagle-import") (part "RESISTOR_?_060310K"))
    )
    (comp (ref "R48")
      (value "RESISTOR_0603_75K")
      (footprint "eagle-import:0603-RES")
      (fields
        (field (name "MANUFACTURER") "Yageo")
        (field (name "MPN") "RT0603BRE0775KL")
        (field (name "POWER") "0.1W")
        (field (name "RESISTANCE") "75k")
      )
      (libsource (lib "eagle-import") (part "RESISTOR_?_060375K"))
    )
    (comp (ref "R49")
      (value "RESISTOR_0603_33.2K")
      (footprint "eagle-import:0603-RES")
      (fields
        (field (name "MANUFACTURER") "Panasonic Electronic Components")
        (field (name "MPN") "ERJ-PB3B3322V")
        (field (name "POWER") "0.1W")
        (field (name "RESISTANCE") "33.2k")
      )
      (libsource (lib "eagle-import") (part "RESISTOR_?_060333.2K"))
    )
    (comp (ref "R50")
      (value "RESISTOR_0603_33.2K")
      (footprint "eagle-import:0603-RES")
      (fields
        (field (name "MANUFACTURER") "Panasonic Electronic Components")
        (field (name "MPN") "ERJ-PB3B3322V")
        (field (name "POWER") "0.1W")
        (field (name "RESISTANCE") "33.2k")
      )
      (libsource (lib "eagle-import") (part "RESISTOR_?_060333.2K"))
    )
    (comp (ref "R55")
      (value "RESISTOR_0603_1K")
      (footprint "eagle-import:0603-RES")
      (fields
        (field (name "MANUFACTURER") "Yageo")
        (field (name "MPN") "RC0603FR-071KL")
        (field (name "POWER") "0.1W")
        (field (name "RESISTANCE") "1k")
      )
      (libsource (lib "eagle-import") (part "RESISTOR_?_06031K"))
    )
    (comp (ref "U16")
      (value "LTC3639")
      (footprint "eagle-import:MSE16(12)")
      (fields (field (name "MPN") "LTC3639EMSE#TRPBF ") (field (name "MANUFACTURER") "Analog Devices Inc."))
      (libsource (lib "eagle-import") (part "LTC3639"))
    )
    (comp (ref "U17")
      (value "VOLTAGE_REGULATOR_ADJ_LR8_DPAK")
      (footprint "eagle-import:DPAK(2-7K1S)")
      (fields (field (name "MANUFACTURER") "Microchip Technology") (field (name "MPN") "LR8K4-G"))
      (libsource (lib "eagle-import") (part "VOLTAGE_REGULATOR_ADJ__?DPAKLR8"))
    )
    (comp (ref "U18")
      (value "ISO224B_AIRGAP")
      (footprint "eagle-import:SOIC-08(WIDE,0.295_)-AIRGAP")
      (fields (field (name "MANUFACTURER") "Texas Instruments") (field (name "MPN") "ISO224BDWVR"))
      (libsource (lib "eagle-import") (part "ISO224_AIRGAPB"))
    )
    (comp (ref "U19")
      (value "ISO224B_AIRGAP")
      (footprint "eagle-import:SOIC-08(WIDE,0.295_)-AIRGAP")
      (fields (field (name "MANUFACTURER") "Texas Instruments") (field (name "MPN") "ISO224BDWVR"))
      (libsource (lib "eagle-import") (part "ISO224_AIRGAPB"))
    )
    (comp (ref "C5")
      (value "CAPACITOR_0603_10V_0.1UF")
      (footprint "eagle-import:0603-CAP")
      (fields
        (field (name "CAPACITANCE") "0.1µF")
        (field (name "MANUFACTURER") "Vishay Vitramon")
        (field (name "MPN") "VJ0603Y104JXQPW1BC")
        (field (name "TOLERANCE") "5%")
        (field (name "VOLTAGE") "10V")
      )
      (libsource (lib "eagle-import") (part "CAPACITOR_?_060310V_0.1UF"))
    )
    (comp (ref "C6")
      (value "CAPACITOR_0603_25V_1UF")
      (footprint "eagle-import:0603-CAP")
      (fields
        (field (name "CAPACITANCE") "1µF")
        (field (name "MANUFACTURER") "Samsung Electro-Mechanics")
        (field (name "MPN") "CL10B105KA8NNNC")
        (field (name "TOLERANCE") "10%")
        (field (name "VOLTAGE") "25V")
      )
      (libsource (lib "eagle-import") (part "CAPACITOR_?_060325V_1UF"))
    )
    (comp (ref "C7")
      (value "CAPACITOR_0603_10V_4.7UF")
      (footprint "eagle-import:0603-CAP")
      (fields
        (field (name "CAPACITANCE") "4.7µF")
        (field (name "MANUFACTURER") "Samsung Electro-Mechanics")
        (field (name "MPN") "CL10A475KP8NNNC")
        (field (name "TOLERANCE") "10%")
        (field (name "VOLTAGE") "10V")
      )
      (libsource (lib "eagle-import") (part "CAPACITOR_?_060310V_4.7UF"))
    )
    (comp (ref "C8")
      (value "CAPACITOR_0603_25V_0.1UF")
      (footprint "eagle-import:0603-CAP")
      (fields
        (field (name "CAPACITANCE") "0.1µF")
        (field (name "MANUFACTURER") "Samsung Electro-Mechanics")
        (field (name "MPN") "CL10B104KA8NNNC")
        (field (name "TOLERANCE") "10%")
        (field (name "VOLTAGE") "25V")
      )
      (libsource (lib "eagle-import") (part "CAPACITOR_?_060325V_0.1UF"))
    )
    (comp (ref "C9")
      (value "CAPACITOR_0603_10V_0.1UF")
      (footprint "eagle-import:0603-CAP")
      (fields
        (field (name "CAPACITANCE") "0.1µF")
        (field (name "MANUFACTURER") "Vishay Vitramon")
        (field (name "MPN") "VJ0603Y104JXQPW1BC")
        (field (name "TOLERANCE") "5%")
        (field (name "VOLTAGE") "10V")
      )
      (libsource (lib "eagle-import") (part "CAPACITOR_?_060310V_0.1UF"))
    )
    (comp (ref "D1")
      (value "TVS_8V")
      (footprint "eagle-import:SOT-23")
      (fields
        (field (name "MANUFACTURER") "Vishay General Semiconductor - Diodes Division")
        (field (name "MPN") "GSOT08-E3-08")
        (field (name "VOLTAGE") "8V")
      )
      (libsource (lib "eagle-import") (part "TVS_8V"))
    )
    (comp (ref "D4")
      (value "LED_0603_GREEN")
      (footprint "eagle-import:0603-LED")
      (fields
        (field (name "COLOR") "Green")
        (field (name "MANUFACTURER") "Kingbright")
        (field (name "MPN") "APT1608ZGCK")
      )
      (libsource (lib "eagle-import") (part "LED_?_0603GREEN"))
    )
    (comp (ref "D7")
      (value "SCHOTTKY")
      (footprint "eagle-import:CLP1608-2L")
      (fields
        (field (name "MPN") "VSKY20401608-G4-08")
        (field (name "MANUFACTURER") "Vishay General Semiconductor - Diodes Division")
      )
      (libsource (lib "eagle-import") (part "SCHOTTKY"))
    )
    (comp (ref "D8")
      (value "SCHOTTKY")
      (footprint "eagle-import:CLP1608-2L")
      (fields
        (field (name "MPN") "VSKY20401608-G4-08")
        (field (name "MANUFACTURER") "Vishay General Semiconductor - Diodes Division")
      )
      (libsource (lib "eagle-import") (part "SCHOTTKY"))
    )
    (comp (ref "D9")
      (value "LED_0603_BLUE")
      (footprint "eagle-import:0603-LED")
      (fields
        (field (name "COLOR") "Blue")
        (field (name "MANUFACTURER") "Kingbright")
        (field (name "MPN") "APT1608VBC/D")
      )
      (libsource (lib "eagle-import") (part "LED_?_0603BLUE"))
    )
    (comp (ref "D11")
      (value "LED_0603_BLUE")
      (footprint "eagle-import:0603-LED")
      (fields
        (field (name "COLOR") "Blue")
        (field (name "MANUFACTURER") "Kingbright")
        (field (name "MPN") "APT1608VBC/D")
      )
      (libsource (lib "eagle-import") (part "LED_?_0603BLUE"))
    )
    (comp (ref "D12")
      (value "LED_0603_WHITE")
      (footprint "eagle-import:0603-LED")
      (fields
        (field (name "COLOR") "White")
        (field (name "MANUFACTURER") "Bivar Inc.")
        (field (name "MPN") "SM0603UWC")
      )
      (libsource (lib "eagle-import") (part "LED_?_0603WHITE"))
    )
    (comp (ref "F2")
      (value "FUSE_0885_1.25")
      (footprint "eagle-import:0885")
      (fields
        (field (name "CURRENT") "1.25A")
        (field (name "MANUFACTURER") "Littelfuse Inc.")
        (field (name "MPN") "08851.25DR")
        (field (name "VOLTAGE") "500V")
      )
      (libsource (lib "eagle-import") (part "FUSE_?_08851.25"))
    )
    (comp (ref "F6")
      (value "FUSE_0885_1.25")
      (footprint "eagle-import:0885")
      (fields
        (field (name "CURRENT") "1.25A")
        (field (name "MANUFACTURER") "Littelfuse Inc.")
        (field (name "MPN") "08851.25DR")
        (field (name "VOLTAGE") "500V")
      )
      (libsource (lib "eagle-import") (part "FUSE_?_08851.25"))
    )
    (comp (ref "J3")
      (value "CONNECTOR-8_MF_T_V_")
      (footprint "eagle-import:MOLEX_MICROFIT_PTH_VERTICAL_08_DUAL")
      (fields (field (name "MPN") "2068320823") (field (name "MANUFACTURER") "Molex"))
      (libsource (lib "eagle-import") (part "CONNECTOR-8_?_MF_T_V"))
    )
    (comp (ref "J5")
      (value "CONNECTOR-4__")
      (footprint "eagle-import:MOLEX_MICROFIT_PTH_VERTICAL_04_DUAL")
      (fields (field (name "MPN") "2068320423") (field (name "MANUFACTURER") "Molex"))
      (libsource (lib "eagle-import") (part "CONNECTOR-4_?_"))
    )
    (comp (ref "K4")
      (value "RELAY_SPST_NC_POLARIZED_3550_12")
      (footprint "eagle-import:335X")
      (fields (field (name "MANUFACTURER") "Comus International") (field (name "MPN") "3350-4275-126"))
      (libsource (lib "eagle-import") (part "RELAY_SPST_NC_POLARIZED_?3550_12"))
    )
    (comp (ref "K5")
      (value "RELAY_SPST_NO_3550_12")
      (footprint "eagle-import:335X")
      (fields (field (name "MANUFACTURER") "Comus International") (field (name "MPN") "3350-1275-126"))
      (libsource (lib "eagle-import") (part "RELAY_SPST_NO_?3550_12"))
    )
    (comp (ref "Q2")
      (value "TRANSISTOR_N_MOS__PMV15ENEA")
      (footprint "eagle-import:SOT-23")
      (fields (field (name "MANUFACTURER") "Nexperia USA Inc.") (field (name "MPN") "PMV15ENEAR"))
      (libsource (lib "eagle-import") (part "TRANSISTOR_N_MOS_?_PMV15ENEA"))
    )
    (comp (ref "R27")
      (value "RESISTOR_0805_12.4")
      (footprint "eagle-import:0805-RES")
      (fields
        (field (name "MANUFACTURER") "  Panasonic Electronic Components")
        (field (name "MPN") "ERJ-6ENF12R4V")
        (field (name "POWER") ".125W")
        (field (name "RESISTANCE") "12.4")
      )
      (libsource (lib "eagle-import") (part "RESISTOR_?_080512.4"))
    )
    (comp (ref "R35")
      (value "RESISTOR_0603_1K")
      (footprint "eagle-import:0603-RES")
      (fields
        (field (name "MANUFACTURER") "Yageo")
        (field (name "MPN") "RC0603FR-071KL")
        (field (name "POWER") "0.1W")
        (field (name "RESISTANCE") "1k")
      )
      (libsource (lib "eagle-import") (part "RESISTOR_?_06031K"))
    )
    (comp (ref "R36")
      (value "RESISTOR_0603_1K")
      (footprint "eagle-import:0603-RES")
      (fields
        (field (name "MANUFACTURER") "Yageo")
        (field (name "MPN") "RC0603FR-071KL")
        (field (name "POWER") "0.1W")
        (field (name "RESISTANCE") "1k")
      )
      (libsource (lib "eagle-import") (part "RESISTOR_?_06031K"))
    )
    (comp (ref "R37")
      (value "RESISTOR_0603_10")
      (footprint "eagle-import:0603-RES")
      (fields
        (field (name "MANUFACTURER") "Yageo")
        (field (name "MPN") "RC0603FR-0710RL")
        (field (name "POWER") "0.1W")
        (field (name "RESISTANCE") "10")
      )
      (libsource (lib "eagle-import") (part "RESISTOR_?_060310"))
    )
    (comp (ref "R38")
      (value "RESISTOR_0603_10K")
      (footprint "eagle-import:0603-RES")
      (fields
        (field (name "MANUFACTURER") "Yageo")
        (field (name "MPN") "RC0603FR-0710KL")
        (field (name "POWER") "0.1W")
        (field (name "RESISTANCE") "10k")
      )
      (libsource (lib "eagle-import") (part "RESISTOR_?_060310K"))
    )
    (comp (ref "R39")
      (value "RESISTOR_GND_750")
      (footprint "eagle-import:B20")
      (fields
        (field (name "MANUFACTURER") "Ohmite")
        (field (name "MPN") "B20J750E")
        (field (name "POWER") "20W")
        (field (name "RESISTANCE") "750")
      )
      (libsource (lib "eagle-import") (part "RESISTOR_GND_750"))
    )
    (comp (ref "R40")
      (value "RESISTOR_GND_10K")
      (footprint "eagle-import:B20")
      (fields
        (field (name "MANUFACTURER") "Ohmite")
        (field (name "MPN") "B20J10KE")
        (field (name "POWER") "20W")
        (field (name "RESISTANCE") "10k")
      )
      (libsource (lib "eagle-import") (part "RESISTOR_GND_10K"))
    )
    (comp (ref "R41")
      (value "RESISTOR_GND_10K")
      (footprint "eagle-import:B20")
      (fields
        (field (name "MANUFACTURER") "Ohmite")
        (field (name "MPN") "B20J10KE")
        (field (name "POWER") "20W")
        (field (name "RESISTANCE") "10k")
      )
      (libsource (lib "eagle-import") (part "RESISTOR_GND_10K"))
    )
    (comp (ref "R42")
      (value "RESISTOR_GND_10K")
      (footprint "eagle-import:B20")
      (fields
        (field (name "MANUFACTURER") "Ohmite")
        (field (name "MPN") "B20J10KE")
        (field (name "POWER") "20W")
        (field (name "RESISTANCE") "10k")
      )
      (libsource (lib "eagle-import") (part "RESISTOR_GND_10K"))
    )
    (comp (ref "R52")
      (value "RESISTOR_0603_1K")
      (footprint "eagle-import:0603-RES")
      (fields
        (field (name "MANUFACTURER") "Yageo")
        (field (name "MPN") "RC0603FR-071KL")
        (field (name "POWER") "0.1W")
        (field (name "RESISTANCE") "1k")
      )
      (libsource (lib "eagle-import") (part "RESISTOR_?_06031K"))
    )
    (comp (ref "R53")
      (value "RESISTOR_0603_1K")
      (footprint "eagle-import:0603-RES")
      (fields
        (field (name "MANUFACTURER") "Yageo")
        (field (name "MPN") "RC0603FR-071KL")
        (field (name "POWER") "0.1W")
        (field (name "RESISTANCE") "1k")
      )
      (libsource (lib "eagle-import") (part "RESISTOR_?_06031K"))
    )
    (comp (ref "R54")
      (value "RESISTOR_0603_1K")
      (footprint "eagle-import:0603-RES")
      (fields
        (field (name "MANUFACTURER") "Yageo")
        (field (name "MPN") "RC0603FR-071KL")
        (field (name "POWER") "0.1W")
        (field (name "RESISTANCE") "1k")
      )
      (libsource (lib "eagle-import") (part "RESISTOR_?_06031K"))
    )
    (comp (ref "R63")
      (value "RESISTOR_0603_1K")
      (footprint "eagle-import:0603-RES")
      (fields
        (field (name "MANUFACTURER") "Yageo")
        (field (name "MPN") "RC0603FR-071KL")
        (field (name "POWER") "0.1W")
        (field (name "RESISTANCE") "1k")
      )
      (libsource (lib "eagle-import") (part "RESISTOR_?_06031K"))
    )
    (comp (ref "TP1")
      (value "TEST_POINT")
      (footprint "eagle-import:MICRO_MINIATURE")
      (fields (field (name "MPN") "5015") (field (name "MANUFACTURER") "Keystone Electronics"))
      (libsource (lib "eagle-import") (part "TEST_POINT"))
    )
    (comp (ref "TP2")
      (value "TEST_POINT")
      (footprint "eagle-import:MICRO_MINIATURE")
      (fields (field (name "MPN") "5015") (field (name "MANUFACTURER") "Keystone Electronics"))
      (libsource (lib "eagle-import") (part "TEST_POINT"))
    )
    (comp (ref "TP3")
      (value "TEST_POINT")
      (footprint "eagle-import:MICRO_MINIATURE")
      (fields (field (name "MPN") "5015") (field (name "MANUFACTURER") "Keystone Electronics"))
      (libsource (lib "eagle-import") (part "TEST_POINT"))
    )
    (comp (ref "TP4")
      (value "TEST_POINT")
      (footprint "eagle-import:MICRO_MINIATURE")
      (fields (field (name "MPN") "5015") (field (name "MANUFACTURER") "Keystone Electronics"))
      (libsource (lib "eagle-import") (part "TEST_POINT"))
    )
    (comp (ref "TP5")
      (value "TEST_POINT")
      (footprint "eagle-import:MICRO_MINIATURE")
      (fields (field (name "MPN") "5015") (field (name "MANUFACTURER") "Keystone Electronics"))
      (libsource (lib "eagle-import") (part "TEST_POINT"))
    )
    (comp (ref "TP6")
      (value "TEST_POINT")
      (footprint "eagle-import:MICRO_MINIATURE")
      (fields (field (name "MPN") "5015") (field (name "MANUFACTURER") "Keystone Electronics"))
      (libsource (lib "eagle-import") (part "TEST_POINT"))
    )
    (comp (ref "TP7")
      (value "TEST_POINT")
      (footprint "eagle-import:MICRO_MINIATURE")
      (fields (field (name "MPN") "5015") (field (name "MANUFACTURER") "Keystone Electronics"))
      (libsource (lib "eagle-import") (part "TEST_POINT"))
    )
    (comp (ref "TP8")
      (value "TEST_POINT")
      (footprint "eagle-import:MICRO_MINIATURE")
      (fields (field (name "MPN") "5015") (field (name "MANUFACTURER") "Keystone Electronics"))
      (libsource (lib "eagle-import") (part "TEST_POINT"))
    )
    (comp (ref "TP9")
      (value "TEST_POINT")
      (footprint "eagle-import:MICRO_MINIATURE")
      (fields (field (name "MPN") "5015") (field (name "MANUFACTURER") "Keystone Electronics"))
      (libsource (lib "eagle-import") (part "TEST_POINT"))
    )
    (comp (ref "TP10")
      (value "TEST_POINT")
      (footprint "eagle-import:MICRO_MINIATURE")
      (fields (field (name "MPN") "5015") (field (name "MANUFACTURER") "Keystone Electronics"))
      (libsource (lib "eagle-import") (part "TEST_POINT"))
    )
    (comp (ref "TP11")
      (value "TEST_POINT")
      (footprint "eagle-import:MICRO_MINIATURE")
      (fields (field (name "MPN") "5015") (field (name "MANUFACTURER") "Keystone Electronics"))
      (libsource (lib "eagle-import") (part "TEST_POINT"))
    )
    (comp (ref "TP12")
      (value "TEST_POINT")
      (footprint "eagle-import:MICRO_MINIATURE")
      (fields (field (name "MPN") "5015") (field (name "MANUFACTURER") "Keystone Electronics"))
      (libsource (lib "eagle-import") (part "TEST_POINT"))
    )
    (comp (ref "TP13")
      (value "TEST_POINT")
      (footprint "eagle-import:MICRO_MINIATURE")
      (fields (field (name "MPN") "5015") (field (name "MANUFACTURER") "Keystone Electronics"))
      (libsource (lib "eagle-import") (part "TEST_POINT"))
    )
    (comp (ref "TP14")
      (value "TEST_POINT")
      (footprint "eagle-import:MICRO_MINIATURE")
      (fields (field (name "MPN") "5015") (field (name "MANUFACTURER") "Keystone Electronics"))
      (libsource (lib "eagle-import") (part "TEST_POINT"))
    )
    (comp (ref "TP15")
      (value "TEST_POINT")
      (footprint "eagle-import:MICRO_MINIATURE")
      (fields (field (name "MPN") "5015") (field (name "MANUFACTURER") "Keystone Electronics"))
      (libsource (lib "eagle-import") (part "TEST_POINT"))
    )
    (comp (ref "TP16")
      (value "TEST_POINT")
      (footprint "eagle-import:MICRO_MINIATURE")
      (fields (field (name "MPN") "5015") (field (name "MANUFACTURER") "Keystone Electronics"))
      (libsource (lib "eagle-import") (part "TEST_POINT"))
    )
    (comp (ref "TP18")
      (value "TEST_POINT")
      (footprint "eagle-import:MICRO_MINIATURE")
      (fields (field (name "MPN") "5015") (field (name "MANUFACTURER") "Keystone Electronics"))
      (libsource (lib "eagle-import") (part "TEST_POINT"))
    )
    (comp (ref "TP19")
      (value "TEST_POINT")
      (footprint "eagle-import:MICRO_MINIATURE")
      (fields (field (name "MPN") "5015") (field (name "MANUFACTURER") "Keystone Electronics"))
      (libsource (lib "eagle-import") (part "TEST_POINT"))
    )
    (comp (ref "TP20")
      (value "TEST_POINT")
      (footprint "eagle-import:MICRO_MINIATURE")
      (fields (field (name "MPN") "5015") (field (name "MANUFACTURER") "Keystone Electronics"))
      (libsource (lib "eagle-import") (part "TEST_POINT"))
    )
    (comp (ref "U$1")
      (value "RELAY_SOLIDSTATE_NO_AG")
      (footprint "eagle-import:DIP-4_AIRGAP")
      (fields (field (name "MPN") "AQY214EHA") (field (name "MANUFACTURER") "Panasonic Inustrial Devices"))
      (libsource (lib "eagle-import") (part "RELAY_SOLIDSTATE_NO_?AG"))
    )
    (comp (ref "U$31")
      (value "CONNECTOR-5_MICRO_V6S_")
      (footprint "eagle-import:MOLEX_MICROFIT_PTH_VERTICAL_06_SINGLE_SPACED")
      (fields (field (name "MPN") "2165713006") (field (name "MANUFACTURER") "Molex"))
      (libsource (lib "eagle-import") (part "CONNECTOR-5_?_MICRO_V6S"))
    )
    (comp (ref "U$33")
      (value "CONNECTOR-5_MICRO_V7S_")
      (footprint "eagle-import:MOLEX_MICROFIT_PTH_VERTICAL_07_SINGLE_SPACED")
      (fields (field (name "MPN") "2165713007") (field (name "MANUFACTURER") "Molex"))
      (libsource (lib "eagle-import") (part "CONNECTOR-5_?_MICRO_V7S"))
    )
    (comp (ref "U2")
      (value "VOLTAGE_REGULATOR_SOT223_5V")
      (footprint "eagle-import:SOT223")
      (fields (field (name "MANUFACTURER") "STMicroelectronics") (field (name "MPN") "LDL1117S50R"))
      (libsource (lib "eagle-import") (part "VOLTAGE_REGULATOR_?_SOT2235V"))
    )
    (comp (ref "U15")
      (value "LOGICGATE_INVERTER_DCKR")
      (footprint "eagle-import:SC-70-5")
      (fields (field (name "MANUFACTURER") "Texas Instruments") (field (name "MPN") "SN74LVC1G04DCKR"))
      (libsource (lib "eagle-import") (part "LOGICGATE_INVERTER_DCKR"))
    )
  )
  (nets
    (net (code "1") (name "+12V") (class "Default")
      (node (ref "C6") (pin "1") (pinfunction "1_1") (pintype "passive"))
      (node (ref "C8") (pin "1") (pinfunction "1_1") (pintype "passive"))
      (node (ref "J3") (pin "1") (pinfunction "1_1") (pintype "passive"))
      (node (ref "R35") (pin "2") (pinfunction "2_2") (pintype "passive"))
      (node (ref "TP1") (pin "1") (pinfunction "P$1_1") (pintype "passive"))
      (node (ref "U2") (pin "3") (pinfunction "IN_3") (pintype "power_in"))
    )
    (net (code "2") (name "DCDC+") (class "Default")
      (node (ref "F1") (pin "L1") (pinfunction "1_L1") (pintype "passive"))
      (node (ref "F1") (pin "L2") (pinfunction "1_L2") (pintype "passive"))
      (node (ref "J5") (pin "1") (pinfunction "1_1") (pintype "passive"))
      (node (ref "J5") (pin "3") (pinfunction "3_3") (pintype "passive"))
      (node (ref "R30") (pin "2") (pinfunction "2_2") (pintype "passive"))
      (node (ref "TP9") (pin "1") (pinfunction "P$1_1") (pintype "passive"))
    )
    (net (code "3") (name "DCDC-") (class "Default")
      (node (ref "C26") (pin "-") (pinfunction "MINUS_-") (pintype "passive"))
      (node (ref "C27") (pin "1") (pinfunction "1_1") (pintype "passive"))
      (node (ref "C28") (pin "1") (pinfunction "1_1") (pintype "passive"))
      (node (ref "C29") (pin "1") (pinfunction "1_1") (pintype "passive"))
      (node (ref "D5") (pin "1") (pinfunction "C_1") (pintype "passive"))
      (node (ref "J5") (pin "2") (pinfunction "2_2") (pintype "passive"))
      (node (ref "J5") (pin "4") (pinfunction "4_4") (pintype "passive"))
      (node (ref "TP10") (pin "1") (pinfunction "P$1_1") (pintype "passive"))
      (node (ref "U10") (pin "7") (pinfunction "-OUT_7") (pintype "power_in"))
      (node (ref "U10") (pin "9") (pinfunction "-OUT_9") (pintype "power_in"))
    )
    (net (code "4") (name "ENABLE") (class "Default")
      (node (ref "U10") (pin "3") (pinfunction "EN_3") (pintype "input"))
      (node (ref "U11") (pin "4") (pinfunction "CONTACT2_4") (pintype "bidirectional"))
    )
    (net (code "5") (name "GND") (class "Default")
      (node (ref "C10") (pin "2") (pinfunction "2_2") (pintype "passive"))
      (node (ref "C11") (pin "2") (pinfunction "2_2") (pintype "passive"))
      (node (ref "C41") (pin "2") (pinfunction "2_2") (pintype "passive"))
      (node (ref "C42") (pin "2") (pinfunction "2_2") (pintype "passive"))
      (node (ref "C43") (pin "2") (pinfunction "2_2") (pintype "passive"))
      (node (ref "C44") (pin "2") (pinfunction "2_2") (pintype "passive"))
      (node (ref "C5") (pin "2") (pinfunction "2_2") (pintype "passive"))
      (node (ref "C6") (pin "2") (pinfunction "2_2") (pintype "passive"))
      (node (ref "C7") (pin "2") (pinfunction "2_2") (pintype "passive"))
      (node (ref "C8") (pin "2") (pinfunction "2_2") (pintype "passive"))
      (node (ref "C9") (pin "2") (pinfunction "2_2") (pintype "passive"))
      (node (ref "D1") (pin "1") (pinfunction "A_1") (pintype "passive"))
      (node (ref "D11") (pin "1") (pinfunction "C_1") (pintype "passive"))
      (node (ref "D12") (pin "1") (pinfunction "C_1") (pintype "passive"))
      (node (ref "D2") (pin "1") (pinfunction "C_1") (pintype "passive"))
      (node (ref "D3") (pin "1") (pinfunction "C_1") (pintype "passive"))
      (node (ref "D4") (pin "1") (pinfunction "C_1") (pintype "passive"))
      (node (ref "D7") (pin "2") (pinfunction "A_2") (pintype "passive"))
      (node (ref "D9") (pin "1") (pinfunction "C_1") (pintype "passive"))
      (node (ref "J3") (pin "4") (pinfunction "4_4") (pintype "passive"))
      (node (ref "K4") (pin "3") (pinfunction "COIL-_3") (pintype "bidirectional"))
      (node (ref "Q2") (pin "2") (pinfunction "S_2") (pintype "passive"))
      (node (ref "R38") (pin "1") (pinfunction "1_1") (pintype "passive"))
      (node (ref "R46") (pin "1") (pinfunction "1_1") (pintype "passive"))
      (node (ref "R51") (pin "1") (pinfunction "1_1") (pintype "passive"))
      (node (ref "TP3") (pin "1") (pinfunction "P$1_1") (pintype "passive"))
      (node (ref "U$1") (pin "2") (pinfunction "CONTROL-_2") (pintype "passive"))
      (node (ref "U1") (pin "2") (pinfunction "GND_2") (pintype "power_in"))
      (node (ref "U11") (pin "2") (pinfunction "CONTROL-_2") (pintype "passive"))
      (node (ref "U15") (pin "3") (pinfunction "GND_3") (pintype "power_in"))
      (node (ref "U18") (pin "5") (pinfunction "GND2_5") (pintype "power_in"))
      (node (ref "U19") (pin "5") (pinfunction "GND2_5") (pintype "power_in"))
      (node (ref "U2") (pin "1") (pinfunction "GND_1") (pintype "power_in"))
    )
    (net (code "6") (name "IP+") (class "Default")
      (node (ref "J3") (pin "5") (pinfunction "5_5") (pintype "passive"))
      (node (ref "TP5") (pin "1") (pinfunction "P$1_1") (pintype "passive"))
      (node (ref "U19") (pin "7") (pinfunction "OUTP_7") (pintype "output"))
    )
    (net (code "7") (name "IP-") (class "Default")
      (node (ref "J3") (pin "6") (pinfunction "6_6") (pintype "passive"))
      (node (ref "TP6") (pin "1") (pinfunction "P$1_1") (pintype "passive"))
      (node (ref "U19") (pin "6") (pinfunction "OUTN_6") (pintype "output"))
    )
    (net (code "8") (name "IT+") (class "Default")
      (node (ref "J3") (pin "7") (pinfunction "7_7") (pintype "passive"))
      (node (ref "TP7") (pin "1") (pinfunction "P$1_1") (pintype "passive"))
      (node (ref "U18") (pin "7") (pinfunction "OUTP_7") (pintype "output"))
    )
    (net (code "9") (name "IT-") (class "Default")
      (node (ref "J3") (pin "8") (pinfunction "8_8") (pintype "passive"))
      (node (ref "TP8") (pin "1") (pinfunction "P$1_1") (pintype "passive"))
      (node (ref "U18") (pin "6") (pinfunction "OUTN_6") (pintype "output"))
    )
    (net (code "10") (name "LED+") (class "Default")
      (node (ref "R63") (pin "2") (pinfunction "2_2") (pintype "passive"))
      (node (ref "U$31") (pin "3") (pinfunction "3_3") (pintype "passive"))
    )
    (net (code "11") (name "Net-(C26-PLUS)") (class "Default")
      (node (ref "C26") (pin "+") (pinfunction "PLUS_+") (pintype "passive"))
      (node (ref "C27") (pin "2") (pinfunction "2_2") (pintype "passive"))
      (node (ref "C28") (pin "2") (pinfunction "2_2") (pintype "passive"))
      (node (ref "C29") (pin "2") (pinfunction "2_2") (pintype "passive"))
      (node (ref "F1") (pin "R1") (pinfunction "2_R1") (pintype "passive"))
      (node (ref "F1") (pin "R2") (pinfunction "2_R2") (pintype "passive"))
      (node (ref "U10") (pin "6") (pinfunction "+OUT_6") (pintype "power_in"))
      (node (ref "U10") (pin "8") (pinfunction "+OUT_8") (pintype "power_in"))
    )
    (net (code "12") (name "Net-(C35-Pad2)") (class "Default")
      (node (ref "C35") (pin "2") (pinfunction "2_2") (pintype "passive"))
      (node (ref "R47") (pin "2") (pinfunction "2_2") (pintype "passive"))
    )
    (net (code "13") (name "Net-(D1-C)") (class "Default")
      (node (ref "D1") (pin "3") (pinfunction "C_3") (pintype "passive"))
      (node (ref "R37") (pin "1") (pinfunction "1_1") (pintype "passive"))
      (node (ref "R38") (pin "2") (pinfunction "2_2") (pintype "passive"))
      (node (ref "R52") (pin "2") (pinfunction "2_2") (pintype "passive"))
      (node (ref "U15") (pin "4") (pinfunction "~{IN}_4") (pintype "output"))
    )
    (net (code "14") (name "Net-(D2-A)") (class "Default")
      (node (ref "D2") (pin "2") (pinfunction "A_2") (pintype "passive"))
      (node (ref "R28") (pin "1") (pinfunction "1_1") (pintype "passive"))
    )
    (net (code "15") (name "Net-(D3-A)") (class "Default")
      (node (ref "D3") (pin "2") (pinfunction "A_2") (pintype "passive"))
      (node (ref "R29") (pin "1") (pinfunction "1_1") (pintype "passive"))
    )
    (net (code "16") (name "Net-(D4-A)") (class "Default")
      (node (ref "D4") (pin "2") (pinfunction "A_2") (pintype "passive"))
      (node (ref "R52") (pin "1") (pinfunction "1_1") (pintype "passive"))
    )
    (net (code "17") (name "Net-(D5-A)") (class "Default")
      (node (ref "D5") (pin "2") (pinfunction "A_2") (pintype "passive"))
      (node (ref "R30") (pin "1") (pinfunction "1_1") (pintype "passive"))
    )
    (net (code "18") (name "Net-(D6-A)") (class "Default")
      (node (ref "D6") (pin "2") (pinfunction "A_2") (pintype "passive"))
      (node (ref "R32") (pin "2") (pinfunction "2_2") (pintype "passive"))
    )
    (net (code "19") (name "Net-(D8-A)") (class "Default")
      (node (ref "D8") (pin "2") (pinfunction "A_2") (pintype "passive"))
      (node (ref "K5") (pin "3") (pinfunction "COIL-_3") (pintype "bidirectional"))
      (node (ref "Q2") (pin "3") (pinfunction "D_3") (pintype "passive"))
    )
    (net (code "20") (name "Net-(D9-A)") (class "Default")
      (node (ref "D9") (pin "2") (pinfunction "A_2") (pintype "passive"))
      (node (ref "R35") (pin "1") (pinfunction "1_1") (pintype "passive"))
    )
    (net (code "21") (name "Net-(D10-A)") (class "Default")
      (node (ref "C3") (pin "1") (pinfunction "1_1") (pintype "passive"))
      (node (ref "C31") (pin "1") (pinfunction "1_1") (pintype "passive"))
      (node (ref "D10") (pin "2") (pinfunction "A_2") (pintype "passive"))
      (node (ref "R43") (pin "2") (pinfunction "2_2") (pintype "passive"))
      (node (ref "R47") (pin "1") (pinfunction "1_1") (pintype "passive"))
      (node (ref "U17") (pin "2") (pinfunction "OUT_2") (pintype "power_in"))
    )
    (net (code "22") (name "Net-(D10-C)") (class "Default")
      (node (ref "C32") (pin "1") (pinfunction "1_1") (pintype "passive"))
      (node (ref "C33") (pin "1") (pinfunction "1_1") (pintype "passive"))
      (node (ref "C35") (pin "1") (pinfunction "1_1") (pintype "passive"))
      (node (ref "C4") (pin "1") (pinfunction "1_1") (pintype "passive"))
      (node (ref "D10") (pin "1") (pinfunction "C_1") (pintype "passive"))
      (node (ref "R5") (pin "2") (pinfunction "2_2") (pintype "passive"))
      (node (ref "U16") (pin "3") (pinfunction "VDD_3") (pintype "power_in"))
    )
    (net (code "23") (name "Net-(D11-A)") (class "Default")
      (node (ref "D11") (pin "2") (pinfunction "A_2") (pintype "passive"))
      (node (ref "R53") (pin "2") (pinfunction "2_2") (pintype "passive"))
    )
    (net (code "24") (name "Net-(D12-A)") (class "Default")
      (node (ref "D12") (pin "2") (pinfunction "A_2") (pintype "passive"))
      (node (ref "R54") (pin "1") (pinfunction "1_1") (pintype "passive"))
    )
    (net (code "25") (name "Net-(D13-A)") (class "Default")
      (node (ref "D13") (pin "2") (pinfunction "A_2") (pintype "passive"))
      (node (ref "R55") (pin "1") (pinfunction "1_1") (pintype "passive"))
    )
    (net (code "26") (name "Net-(K4-CONTACT2)") (class "Default")
      (node (ref "K4") (pin "4") (pinfunction "CONTACT2_4") (pintype "bidirectional"))
      (node (ref "R40") (pin "1") (pinfunction "1_1") (pintype "passive"))
    )
    (net (code "27") (name "Net-(K5-CONTACT2)") (class "Default")
      (node (ref "K5") (pin "4") (pinfunction "CONTACT2_4") (pintype "bidirectional"))
      (node (ref "R39") (pin "1") (pinfunction "1_1") (pintype "passive"))
    )
    (net (code "28") (name "Net-(L4-Pad2)") (class "Default")
      (node (ref "L4") (pin "2") (pinfunction "2_2") (pintype "passive"))
      (node (ref "R31") (pin "1") (pinfunction "1_1") (pintype "passive"))
    )
    (net (code "29") (name "Net-(Q2-G)") (class "Default")
      (node (ref "Q2") (pin "1") (pinfunction "G_1") (pintype "passive"))
      (node (ref "R37") (pin "2") (pinfunction "2_2") (pintype "passive"))
    )
    (net (code "30") (name "Net-(R1-Pad1)") (class "Default")
      (node (ref "R1") (pin "1") (pinfunction "1_1") (pintype "passive"))
      (node (ref "R16") (pin "1") (pinfunction "1_1") (pintype "passive"))
    )
    (net (code "31") (name "Net-(R2-Pad1)") (class "Default")
      (node (ref "R2") (pin "1") (pinfunction "1_1") (pintype "passive"))
      (node (ref "R6") (pin "1") (pinfunction "1_1") (pintype "passive"))
    )
    (net (code "32") (name "Net-(R6-Pad2)") (class "Default")
      (node (ref "R6") (pin "2") (pinfunction "2_2") (pintype "passive"))
      (node (ref "R7") (pin "2") (pinfunction "2_2") (pintype "passive"))
    )
    (net (code "33") (name "Net-(R7-Pad1)") (class "Default")
      (node (ref "R7") (pin "1") (pinfunction "1_1") (pintype "passive"))
      (node (ref "R8") (pin "1") (pinfunction "1_1") (pintype "passive"))
    )
    (net (code "34") (name "Net-(R8-Pad2)") (class "Default")
      (node (ref "R8") (pin "2") (pinfunction "2_2") (pintype "passive"))
      (node (ref "R9") (pin "2") (pinfunction "2_2") (pintype "passive"))
    )
    (net (code "35") (name "Net-(R10-Pad1)") (class "Default")
      (node (ref "R10") (pin "1") (pinfunction "1_1") (pintype "passive"))
      (node (ref "R11") (pin "1") (pinfunction "1_1") (pintype "passive"))
      (node (ref "R12") (pin "2") (pinfunction "2_2") (pintype "passive"))
      (node (ref "R13") (pin "2") (pinfunction "2_2") (pintype "passive"))
    )
    (net (code "36") (name "Net-(R10-Pad2)") (class "Default")
      (node (ref "R10") (pin "2") (pinfunction "2_2") (pintype "passive"))
      (node (ref "R11") (pin "2") (pinfunction "2_2") (pintype "passive"))
      (node (ref "R49") (pin "1") (pinfunction "1_1") (pintype "passive"))
      (node (ref "R9") (pin "1") (pinfunction "1_1") (pintype "passive"))
    )
    (net (code "37") (name "Net-(R12-Pad1)") (class "Default")
      (node (ref "R12") (pin "1") (pinfunction "1_1") (pintype "passive"))
      (node (ref "R13") (pin "1") (pinfunction "1_1") (pintype "passive"))
      (node (ref "R14") (pin "2") (pinfunction "2_2") (pintype "passive"))
      (node (ref "R15") (pin "2") (pinfunction "2_2") (pintype "passive"))
    )
    (net (code "38") (name "Net-(R16-Pad2)") (class "Default")
      (node (ref "R16") (pin "2") (pinfunction "2_2") (pintype "passive"))
      (node (ref "R17") (pin "2") (pinfunction "2_2") (pintype "passive"))
    )
    (net (code "39") (name "Net-(R17-Pad1)") (class "Default")
      (node (ref "R17") (pin "1") (pinfunction "1_1") (pintype "passive"))
      (node (ref "R18") (pin "1") (pinfunction "1_1") (pintype "passive"))
    )
    (net (code "40") (name "Net-(R18-Pad2)") (class "Default")
      (node (ref "R18") (pin "2") (pinfunction "2_2") (pintype "passive"))
      (node (ref "R19") (pin "2") (pinfunction "2_2") (pintype "passive"))
    )
    (net (code "41") (name "Net-(R19-Pad1)") (class "Default")
      (node (ref "R19") (pin "1") (pinfunction "1_1") (pintype "passive"))
      (node (ref "R20") (pin "2") (pinfunction "2_2") (pintype "passive"))
      (node (ref "R21") (pin "2") (pinfunction "2_2") (pintype "passive"))
      (node (ref "R50") (pin "1") (pinfunction "1_1") (pintype "passive"))
    )
    (net (code "42") (name "Net-(R20-Pad1)") (class "Default")
      (node (ref "R20") (pin "1") (pinfunction "1_1") (pintype "passive"))
      (node (ref "R21") (pin "1") (pinfunction "1_1") (pintype "passive"))
      (node (ref "R22") (pin "2") (pinfunction "2_2") (pintype "passive"))
      (node (ref "R23") (pin "2") (pinfunction "2_2") (pintype "passive"))
    )
    (net (code "43") (name "Net-(R22-Pad1)") (class "Default")
      (node (ref "R22") (pin "1") (pinfunction "1_1") (pintype "passive"))
      (node (ref "R23") (pin "1") (pinfunction "1_1") (pintype "passive"))
      (node (ref "R24") (pin "2") (pinfunction "2_2") (pintype "passive"))
      (node (ref "R25") (pin "2") (pinfunction "2_2") (pintype "passive"))
    )
    (net (code "44") (name "Net-(U$1-CONTACT1)") (class "Default")
      (node (ref "R27") (pin "2") (pinfunction "2_2") (pintype "passive"))
      (node (ref "U$1") (pin "3") (pinfunction "CONTACT1_3") (pintype "bidirectional"))
    )
    (net (code "45") (name "Net-(U$1-CONTROL+)") (class "Default")
      (node (ref "R36") (pin "1") (pinfunction "1_1") (pintype "passive"))
      (node (ref "U$1") (pin "1") (pinfunction "CONTROL+_1") (pintype "passive"))
    )
    (net (code "46") (name "Net-(U1-DIV)") (class "Default")
      (node (ref "R44") (pin "1") (pinfunction "1_1") (pintype "passive"))
      (node (ref "R46") (pin "2") (pinfunction "2_2") (pintype "passive"))
      (node (ref "U1") (pin "6") (pinfunction "DIV_6") (pintype "bidirectional"))
    )
    (net (code "47") (name "Net-(U1-OUT)") (class "Default")
      (node (ref "R28") (pin "2") (pinfunction "2_2") (pintype "passive"))
      (node (ref "R34") (pin "1") (pinfunction "1_1") (pintype "passive"))
      (node (ref "U1") (pin "4") (pinfunction "OUT_4") (pintype "bidirectional"))
    )
    (net (code "48") (name "Net-(U1-SET)") (class "Default")
      (node (ref "C11") (pin "1") (pinfunction "1_1") (pintype "passive"))
      (node (ref "R51") (pin "2") (pinfunction "2_2") (pintype "passive"))
      (node (ref "U1") (pin "3") (pinfunction "SET_3") (pintype "bidirectional"))
    )
    (net (code "49") (name "Net-(U10-+IN)") (class "Default")
      (node (ref "C1") (pin "1") (pinfunction "1_1") (pintype "passive"))
      (node (ref "C24") (pin "1") (pinfunction "1_1") (pintype "passive"))
      (node (ref "C25") (pin "1") (pinfunction "1_1") (pintype "passive"))
      (node (ref "L4") (pin "1") (pinfunction "1_1") (pintype "passive"))
      (node (ref "L5") (pin "1") (pinfunction "1_1") (pintype "passive"))
      (node (ref "U10") (pin "1") (pinfunction "+IN_1") (pintype "power_in"))
    )
    (net (code "50") (name "Net-(U10-FLT)") (class "Default")
      (node (ref "R32") (pin "1") (pinfunction "1_1") (pintype "passive"))
      (node (ref "U10") (pin "4") (pinfunction "FLT_4") (pintype "output"))
    )
    (net (code "51") (name "Net-(U10-TR)") (class "Default")
      (node (ref "R33") (pin "1") (pinfunction "1_1") (pintype "passive"))
      (node (ref "U10") (pin "2") (pinfunction "TR_2") (pintype "output"))
    )
    (net (code "52") (name "Net-(U11-CONTROL+)") (class "Default")
      (node (ref "R34") (pin "2") (pinfunction "2_2") (pintype "passive"))
      (node (ref "U11") (pin "1") (pinfunction "CONTROL+_1") (pintype "passive"))
    )
    (net (code "53") (name "Net-(U16-ISET)") (class "Default")
      (node (ref "R48") (pin "2") (pinfunction "2_2") (pintype "passive"))
      (node (ref "U16") (pin "11") (pinfunction "ISET_11") (pintype "bidirectional"))
    )
    (net (code "54") (name "Net-(U16-OVLO)") (class "Default")
      (node (ref "R3") (pin "2") (pinfunction "2_2") (pintype "passive"))
      (node (ref "R4") (pin "1") (pinfunction "1_1") (pintype "passive"))
      (node (ref "U16") (pin "12") (pinfunction "OVLO_12") (pintype "input"))
    )
    (net (code "55") (name "Net-(U16-RUN)") (class "Default")
      (node (ref "R4") (pin "2") (pinfunction "2_2") (pintype "passive"))
      (node (ref "R5") (pin "1") (pinfunction "1_1") (pintype "passive"))
      (node (ref "U16") (pin "14") (pinfunction "RUN_14") (pintype "input"))
    )
    (net (code "56") (name "Net-(U16-SS)") (class "Default")
      (node (ref "U16") (pin "10") (pinfunction "SS_10") (pintype "input"))
      (node (ref "U16") (pin "7") (pinfunction "VPRG1_7") (pintype "input"))
    )
    (net (code "57") (name "Net-(U16-SW)") (class "Default")
      (node (ref "L6") (pin "1") (pinfunction "1_1") (pintype "passive"))
      (node (ref "U16") (pin "1") (pinfunction "SW_1") (pintype "power_in"))
    )
    (net (code "58") (name "Net-(U17-ADJ)") (class "Default")
      (node (ref "R43") (pin "1") (pinfunction "1_1") (pintype "passive"))
      (node (ref "R45") (pin "2") (pinfunction "2_2") (pintype "passive"))
      (node (ref "U17") (pin "3") (pinfunction "ADJ_3") (pintype "input"))
    )
    (net (code "59") (name "Net-(U17-IN)") (class "Default")
      (node (ref "C2") (pin "1") (pinfunction "1_1") (pintype "passive"))
      (node (ref "C30") (pin "1") (pinfunction "1_1") (pintype "passive"))
      (node (ref "R26") (pin "2") (pinfunction "2_2") (pintype "passive"))
      (node (ref "U17") (pin "1") (pinfunction "IN_1") (pintype "power_in"))
    )
    (net (code "60") (name "Net-(U18-IN)") (class "Default")
      (node (ref "C49") (pin "1") (pinfunction "1_1") (pintype "passive"))
      (node (ref "R50") (pin "2") (pinfunction "2_2") (pintype "passive"))
      (node (ref "U18") (pin "2") (pinfunction "IN_2") (pintype "input"))
    )
    (net (code "61") (name "Net-(U18-VCAP)") (class "Default")
      (node (ref "C38") (pin "1") (pinfunction "1_1") (pintype "passive"))
      (node (ref "U18") (pin "1") (pinfunction "VCAP_1") (pintype "passive"))
    )
    (net (code "62") (name "Net-(U19-IN)") (class "Default")
      (node (ref "C48") (pin "1") (pinfunction "1_1") (pintype "passive"))
      (node (ref "R49") (pin "2") (pinfunction "2_2") (pintype "passive"))
      (node (ref "U19") (pin "2") (pinfunction "IN_2") (pintype "input"))
    )
    (net (code "63") (name "Net-(U19-VCAP)") (class "Default")
      (node (ref "C45") (pin "1") (pinfunction "1_1") (pintype "passive"))
      (node (ref "U19") (pin "1") (pinfunction "VCAP_1") (pintype "passive"))
    )
    (net (code "64") (name "PACK+") (class "Default")
      (node (ref "K5") (pin "1") (pinfunction "CONTACT1_1") (pintype "bidirectional"))
      (node (ref "TP12") (pin "1") (pinfunction "P$1_1") (pintype "passive"))
      (node (ref "U$1") (pin "4") (pinfunction "CONTACT2_4") (pintype "bidirectional"))
      (node (ref "U$33") (pin "5") (pinfunction "5_5") (pintype "passive"))
    )
    (net (code "65") (name "PACK+FUSED") (class "Default")
      (node (ref "R2") (pin "2") (pinfunction "2_2") (pintype "passive"))
      (node (ref "R27") (pin "1") (pinfunction "1_1") (pintype "passive"))
      (node (ref "TP13") (pin "1") (pinfunction "P$1_1") (pintype "passive"))
    )
    (net (code "66") (name "PRECHARGE_OK") (class "Default")
      (node (ref "J3") (pin "3") (pinfunction "3_3") (pintype "passive"))
      (node (ref "R29") (pin "2") (pinfunction "2_2") (pintype "passive"))
      (node (ref "TP4") (pin "1") (pinfunction "P$1_1") (pintype "passive"))
      (node (ref "U1") (pin "1") (pinfunction "IN_1") (pintype "bidirectional"))
      (node (ref "U15") (pin "2") (pinfunction "IN_2") (pintype "input"))
    )
    (net (code "67") (name "SHDN") (class "Default")
      (node (ref "D7") (pin "1") (pinfunction "C_1") (pintype "passive"))
      (node (ref "D8") (pin "1") (pinfunction "C_1") (pintype "passive"))
      (node (ref "J3") (pin "2") (pinfunction "2_2") (pintype "passive"))
      (node (ref "K4") (pin "2") (pinfunction "COIL+_2") (pintype "bidirectional"))
      (node (ref "K5") (pin "2") (pinfunction "COIL+_2") (pintype "bidirectional"))
      (node (ref "R36") (pin "2") (pinfunction "2_2") (pintype "passive"))
      (node (ref "R54") (pin "2") (pinfunction "2_2") (pintype "passive"))
      (node (ref "TP11") (pin "1") (pinfunction "P$1_1") (pintype "passive"))
    )
    (net (code "68") (name "TS+5V") (class "Default")
      (node (ref "C34") (pin "1") (pinfunction "1_1") (pintype "passive"))
      (node (ref "C36") (pin "1") (pinfunction "1_1") (pintype "passive"))
      (node (ref "C37") (pin "1") (pinfunction "1_1") (pintype "passive"))
      (node (ref "C39") (pin "1") (pinfunction "1_1") (pintype "passive"))
      (node (ref "C40") (pin "1") (pinfunction "1_1") (pintype "passive"))
      (node (ref "C46") (pin "1") (pinfunction "1_1") (pintype "passive"))
      (node (ref "C47") (pin "1") (pinfunction "1_1") (pintype "passive"))
      (node (ref "L6") (pin "2") (pinfunction "2_2") (pintype "passive"))
      (node (ref "R55") (pin "2") (pinfunction "2_2") (pintype "passive"))
      (node (ref "R63") (pin "1") (pinfunction "1_1") (pintype "passive"))
      (node (ref "TP20") (pin "1") (pinfunction "P$1_1") (pintype "passive"))
      (node (ref "U16") (pin "9") (pinfunction "VFB_9") (pintype "input"))
      (node (ref "U18") (pin "3") (pinfunction "VDD1_3") (pintype "power_in"))
      (node (ref "U19") (pin "3") (pinfunction "VDD1_3") (pintype "power_in"))
    )
    (net (code "69") (name "TS+FUSED") (class "Default")
      (node (ref "F6") (pin "2") (pinfunction "2_2") (pintype "passive"))
      (node (ref "L5") (pin "2") (pinfunction "2_2") (pintype "passive"))
      (node (ref "R1") (pin "2") (pinfunction "2_2") (pintype "passive"))
      (node (ref "R26") (pin "1") (pinfunction "1_1") (pintype "passive"))
      (node (ref "R31") (pin "2") (pinfunction "2_2") (pintype "passive"))
      (node (ref "U$33") (pin "4") (pinfunction "4_4") (pintype "passive"))
    )
    (net (code "70") (name "TS+UNFUSED") (class "Default")
      (node (ref "F6") (pin "1") (pinfunction "1_1") (pintype "passive"))
      (node (ref "K4") (pin "1") (pinfunction "CONTACT1_1") (pintype "bidirectional"))
      (node (ref "R39") (pin "2") (pinfunction "2_2") (pintype "passive"))
      (node (ref "R42") (pin "1") (pinfunction "1_1") (pintype "passive"))
      (node (ref "TP14") (pin "1") (pinfunction "P$1_1") (pintype "passive"))
      (node (ref "U$33") (pin "1") (pinfunction "1_1") (pintype "passive"))
      (node (ref "U$33") (pin "2") (pinfunction "2_2") (pintype "passive"))
    )
    (net (code "71") (name "TS-FUSED") (class "Default")
      (node (ref "C1") (pin "2") (pinfunction "2_2") (pintype "passive"))
      (node (ref "C2") (pin "2") (pinfunction "2_2") (pintype "passive"))
      (node (ref "C24") (pin "2") (pinfunction "2_2") (pintype "passive"))
      (node (ref "C25") (pin "2") (pinfunction "2_2") (pintype "passive"))
      (node (ref "C3") (pin "2") (pinfunction "2_2") (pintype "passive"))
      (node (ref "C30") (pin "2") (pinfunction "2_2") (pintype "passive"))
      (node (ref "C31") (pin "2") (pinfunction "2_2") (pintype "passive"))
      (node (ref "C32") (pin "2") (pinfunction "2_2") (pintype "passive"))
      (node (ref "C33") (pin "2") (pinfunction "2_2") (pintype "passive"))
      (node (ref "C34") (pin "2") (pinfunction "2_2") (pintype "passive"))
      (node (ref "C36") (pin "2") (pinfunction "2_2") (pintype "passive"))
      (node (ref "C37") (pin "2") (pinfunction "2_2") (pintype "passive"))
      (node (ref "C38") (pin "2") (pinfunction "2_2") (pintype "passive"))
      (node (ref "C39") (pin "2") (pinfunction "2_2") (pintype "passive"))
      (node (ref "C4") (pin "2") (pinfunction "2_2") (pintype "passive"))
      (node (ref "C40") (pin "2") (pinfunction "2_2") (pintype "passive"))
      (node (ref "C45") (pin "2") (pinfunction "2_2") (pintype "passive"))
      (node (ref "C46") (pin "2") (pinfunction "2_2") (pintype "passive"))
      (node (ref "C47") (pin "2") (pinfunction "2_2") (pintype "passive"))
      (node (ref "C48") (pin "2") (pinfunction "2_2") (pintype "passive"))
      (node (ref "C49") (pin "2") (pinfunction "2_2") (pintype "passive"))
      (node (ref "D13") (pin "1") (pinfunction "C_1") (pintype "passive"))
      (node (ref "D6") (pin "1") (pinfunction "C_1") (pintype "passive"))
      (node (ref "F2") (pin "2") (pinfunction "2_2") (pintype "passive"))
      (node (ref "R14") (pin "1") (pinfunction "1_1") (pintype "passive"))
      (node (ref "R15") (pin "1") (pinfunction "1_1") (pintype "passive"))
      (node (ref "R24") (pin "1") (pinfunction "1_1") (pintype "passive"))
      (node (ref "R25") (pin "1") (pinfunction "1_1") (pintype "passive"))
      (node (ref "R3") (pin "1") (pinfunction "1_1") (pintype "passive"))
      (node (ref "R33") (pin "2") (pinfunction "2_2") (pintype "passive"))
      (node (ref "R39") (pin "3") (pinfunction "3_3") (pintype "passive"))
      (node (ref "R39") (pin "4") (pinfunction "3_4") (pintype "passive"))
      (node (ref "R39") (pin "5") (pinfunction "3_5") (pintype "passive"))
      (node (ref "R39") (pin "6") (pinfunction "3_6") (pintype "passive"))
      (node (ref "R40") (pin "3") (pinfunction "3_3") (pintype "passive"))
      (node (ref "R40") (pin "4") (pinfunction "3_4") (pintype "passive"))
      (node (ref "R40") (pin "5") (pinfunction "3_5") (pintype "passive"))
      (node (ref "R40") (pin "6") (pinfunction "3_6") (pintype "passive"))
      (node (ref "R41") (pin "3") (pinfunction "3_3") (pintype "passive"))
      (node (ref "R41") (pin "4") (pinfunction "3_4") (pintype "passive"))
      (node (ref "R41") (pin "5") (pinfunction "3_5") (pintype "passive"))
      (node (ref "R41") (pin "6") (pinfunction "3_6") (pintype "passive"))
      (node (ref "R42") (pin "3") (pinfunction "3_3") (pintype "passive"))
      (node (ref "R42") (pin "4") (pinfunction "3_4") (pintype "passive"))
      (node (ref "R42") (pin "5") (pinfunction "3_5") (pintype "passive"))
      (node (ref "R42") (pin "6") (pinfunction "3_6") (pintype "passive"))
      (node (ref "R45") (pin "1") (pinfunction "1_1") (pintype "passive"))
      (node (ref "R48") (pin "1") (pinfunction "1_1") (pintype "passive"))
      (node (ref "TP16") (pin "1") (pinfunction "P$1_1") (pintype "passive"))
      (node (ref "U$31") (pin "1") (pinfunction "1_1") (pintype "passive"))
      (node (ref "U$31") (pin "2") (pinfunction "2_2") (pintype "passive"))
      (node (ref "U10") (pin "5") (pinfunction "-IN_5") (pintype "power_in"))
      (node (ref "U11") (pin "3") (pinfunction "CONTACT1_3") (pintype "bidirectional"))
      (node (ref "U16") (pin "16") (pinfunction "GND_16") (pintype "power_in"))
      (node (ref "U16") (pin "6") (pinfunction "VPRG2_6") (pintype "input"))
      (node (ref "U16") (pin "8") (pinfunction "GND_8") (pintype "power_in"))
      (node (ref "U18") (pin "4") (pinfunction "GND1_4") (pintype "power_in"))
      (node (ref "U19") (pin "4") (pinfunction "GND1_4") (pintype "power_in"))
    )
    (net (code "72") (name "TS-UNFUSED") (class "Default")
      (node (ref "F2") (pin "1") (pinfunction "1_1") (pintype "passive"))
      (node (ref "R40") (pin "2") (pinfunction "2_2") (pintype "passive"))
      (node (ref "R41") (pin "1") (pinfunction "1_1") (pintype "passive"))
      (node (ref "TP15") (pin "1") (pinfunction "P$1_1") (pintype "passive"))
      (node (ref "U$31") (pin "5") (pinfunction "5_5") (pintype "passive"))
    )
    (net (code "73") (name "TSMP+") (class "Default")
      (node (ref "R42") (pin "2") (pinfunction "2_2") (pintype "passive"))
      (node (ref "TP18") (pin "1") (pinfunction "P$1_1") (pintype "passive"))
      (node (ref "U$33") (pin "3") (pinfunction "3_3") (pintype "passive"))
    )
    (net (code "74") (name "TSMP-") (class "Default")
      (node (ref "R41") (pin "2") (pinfunction "2_2") (pintype "passive"))
      (node (ref "TP19") (pin "1") (pinfunction "P$1_1") (pintype "passive"))
      (node (ref "U$31") (pin "4") (pinfunction "4_4") (pintype "passive"))
    )
    (net (code "75") (name "VDD") (class "Default")
      (node (ref "C10") (pin "1") (pinfunction "1_1") (pintype "passive"))
      (node (ref "C41") (pin "1") (pinfunction "1_1") (pintype "passive"))
      (node (ref "C42") (pin "1") (pinfunction "1_1") (pintype "passive"))
      (node (ref "C43") (pin "1") (pinfunction "1_1") (pintype "passive"))
      (node (ref "C44") (pin "1") (pinfunction "1_1") (pintype "passive"))
      (node (ref "C5") (pin "1") (pinfunction "1_1") (pintype "passive"))
      (node (ref "C7") (pin "1") (pinfunction "1_1") (pintype "passive"))
      (node (ref "C9") (pin "1") (pinfunction "1_1") (pintype "passive"))
      (node (ref "R44") (pin "2") (pinfunction "2_2") (pintype "passive"))
      (node (ref "R53") (pin "1") (pinfunction "1_1") (pintype "passive"))
      (node (ref "TP2") (pin "1") (pinfunction "P$1_1") (pintype "passive"))
      (node (ref "U1") (pin "5") (pinfunction "V+_5") (pintype "power_in"))
      (node (ref "U15") (pin "5") (pinfunction "VDD_5") (pintype "power_in"))
      (node (ref "U18") (pin "8") (pinfunction "VDD2_8") (pintype "power_in"))
      (node (ref "U19") (pin "8") (pinfunction "VDD2_8") (pintype "power_in"))
      (node (ref "U2") (pin "2") (pinfunction "OUT_2") (pintype "power_in"))
      (node (ref "U2") (pin "4") (pinfunction "OUT_4") (pintype "power_in"))
    )
    (net (code "76") (name "unconnected-(U16-FBO-Pad5)") (class "Default")
      (node (ref "U16") (pin "5") (pinfunction "FBO_5") (pintype "output"))
    )
  )
)
